# uacs.net
KiCad netlist of a schematic drawn in EAGLE
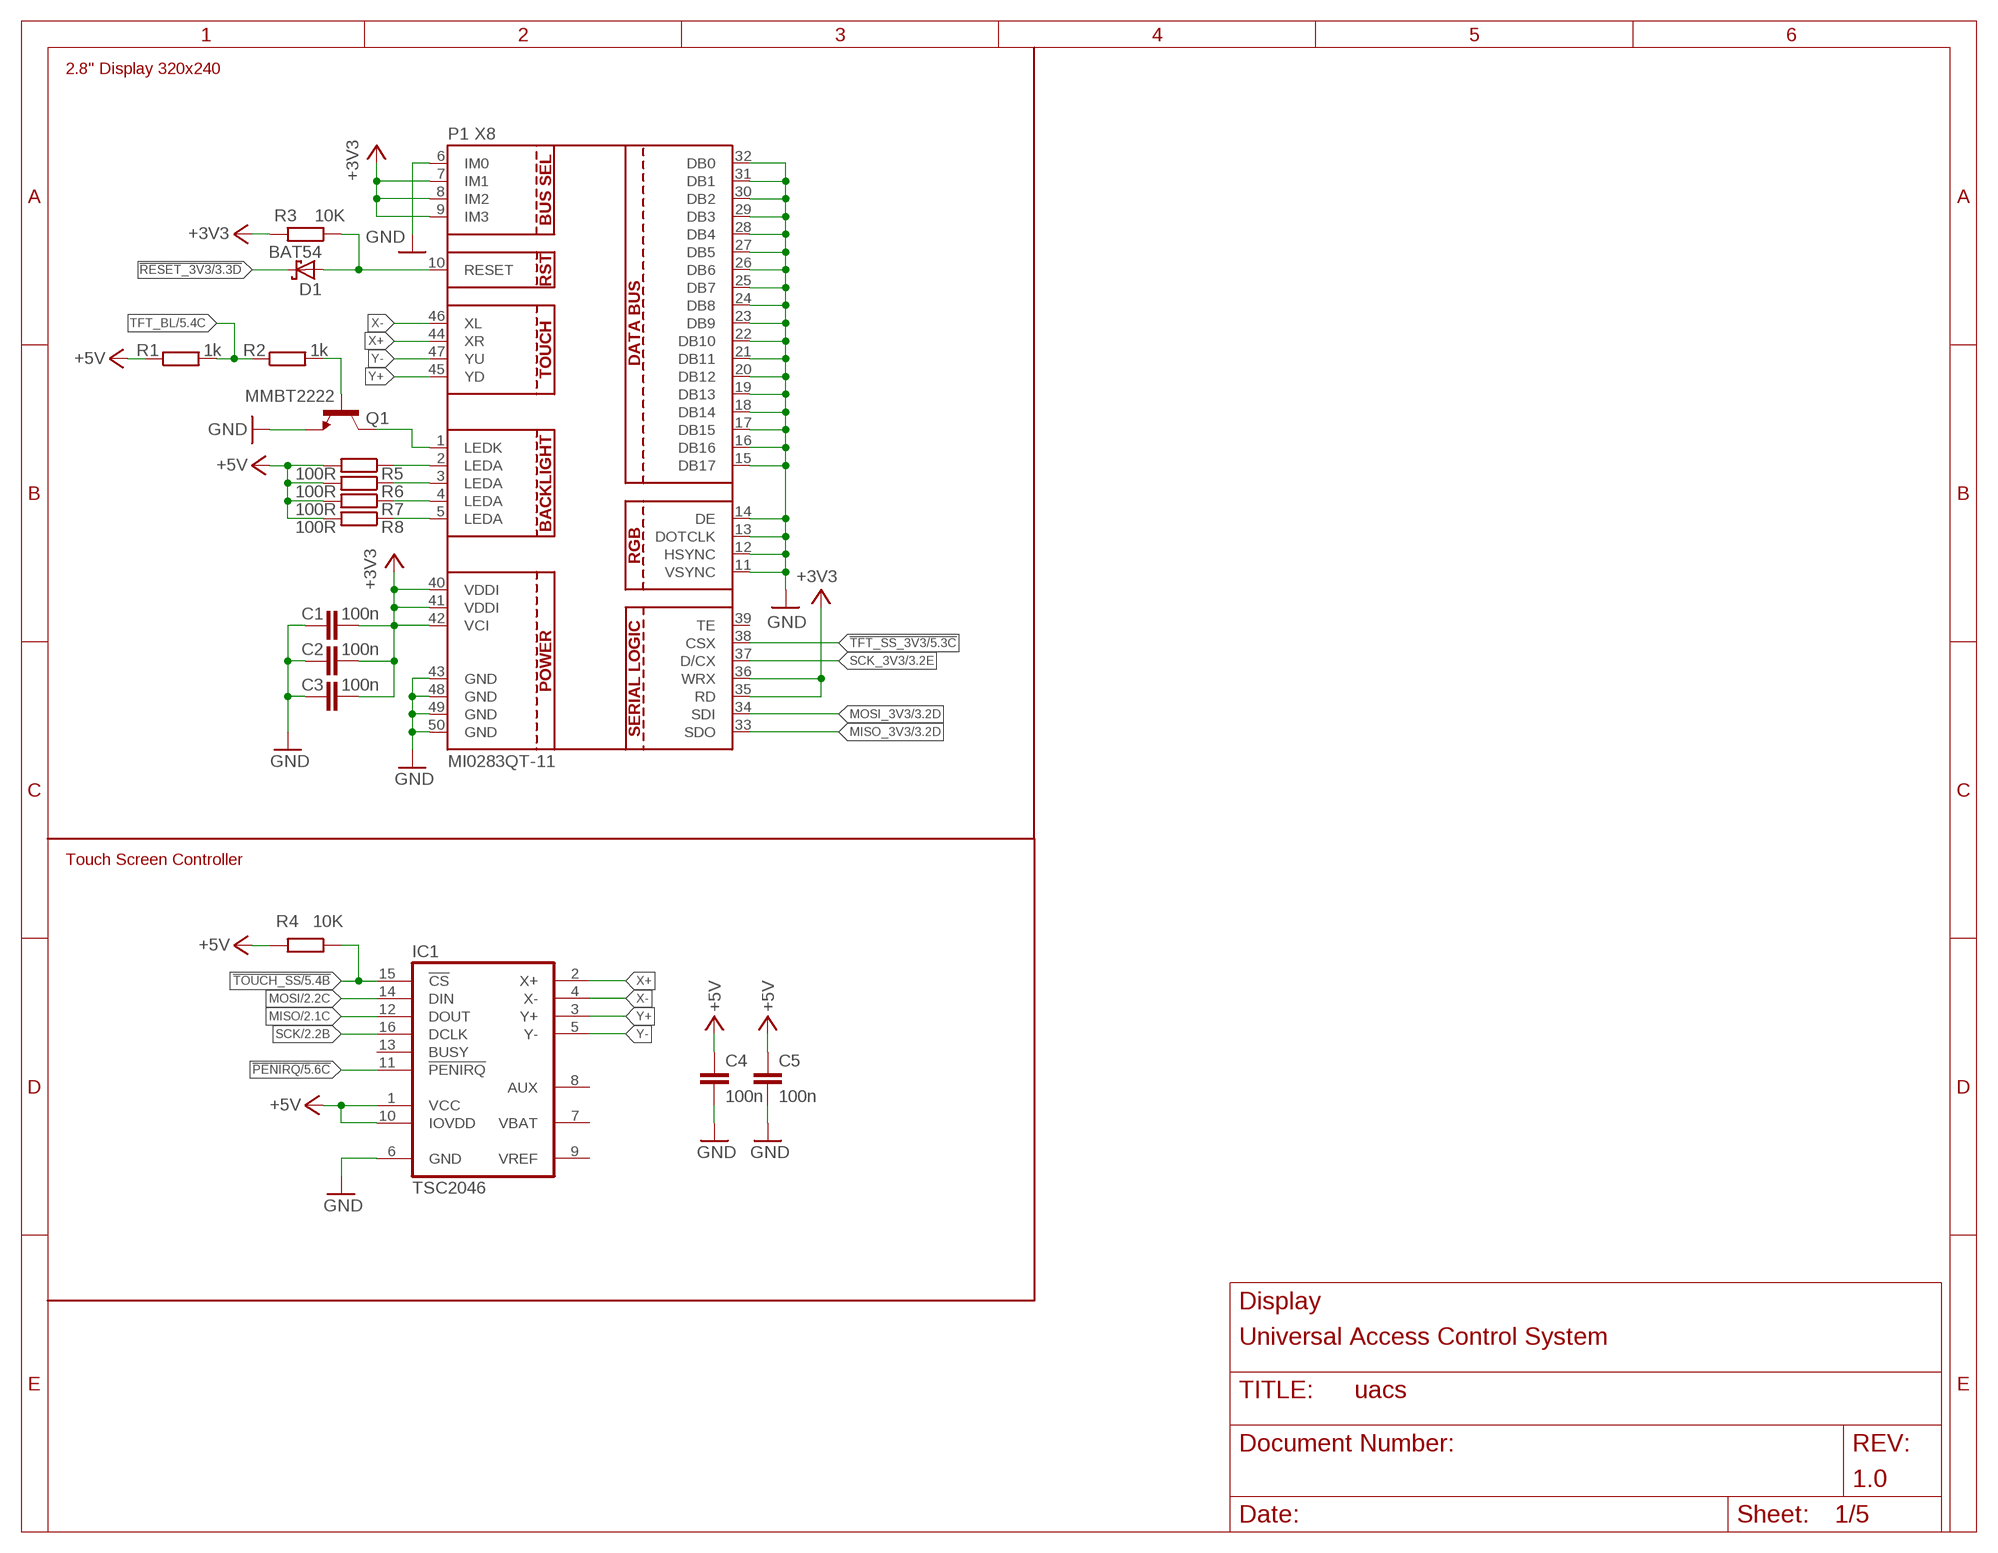
[diagram p0: schematic, sheet 1]
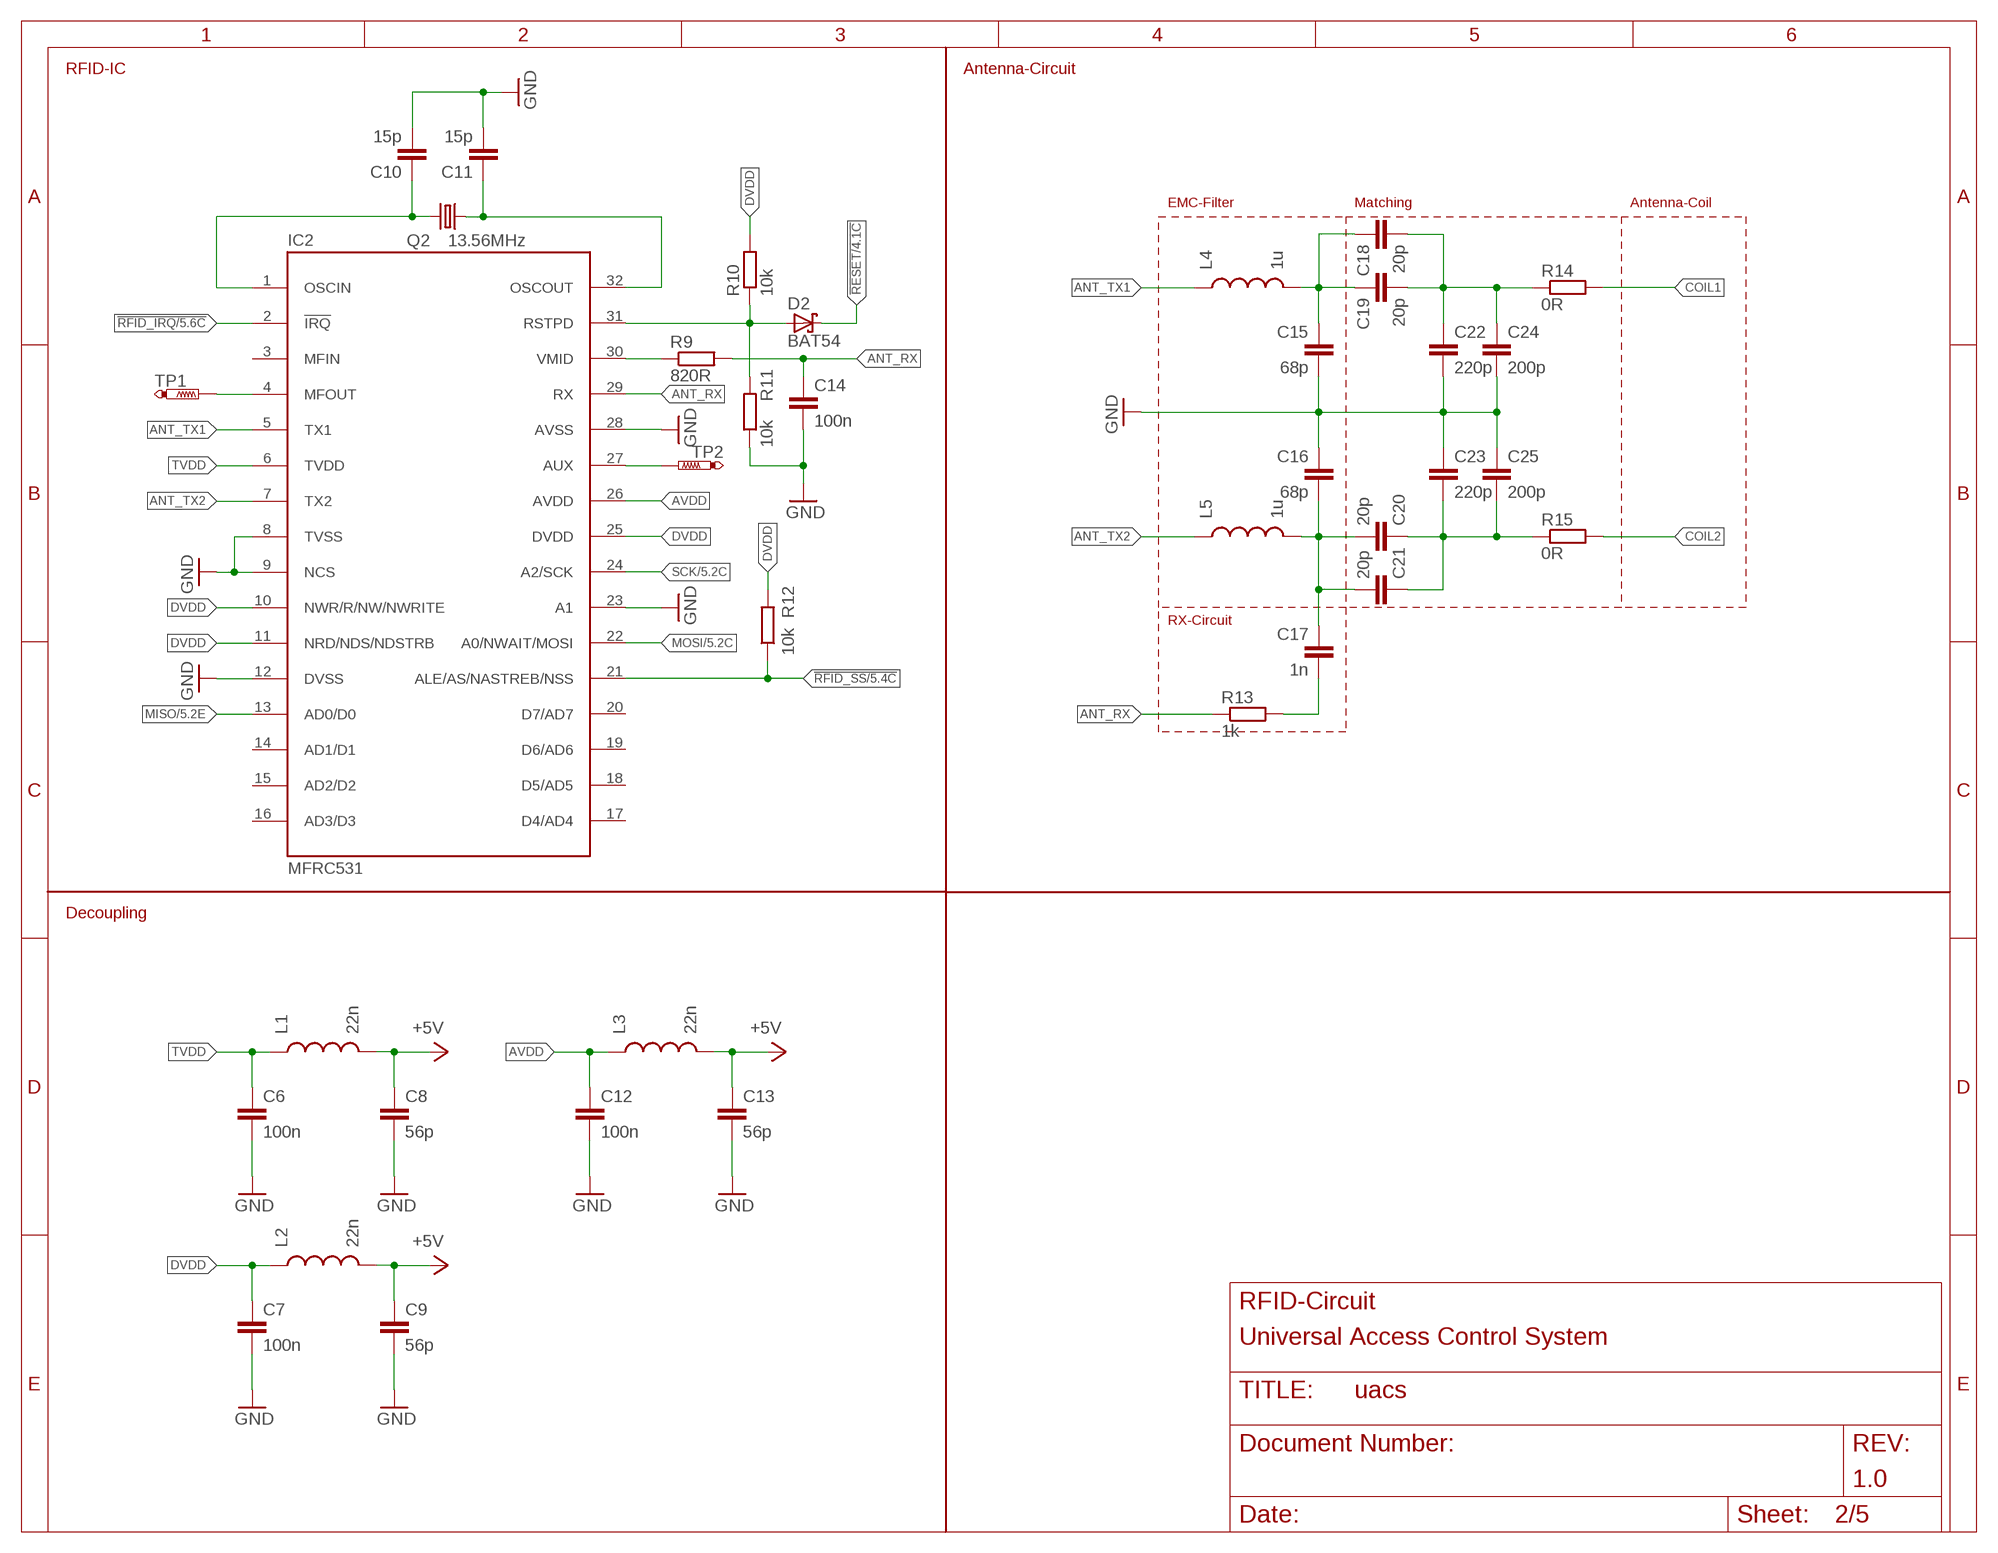
[diagram p1: schematic, sheet 2]
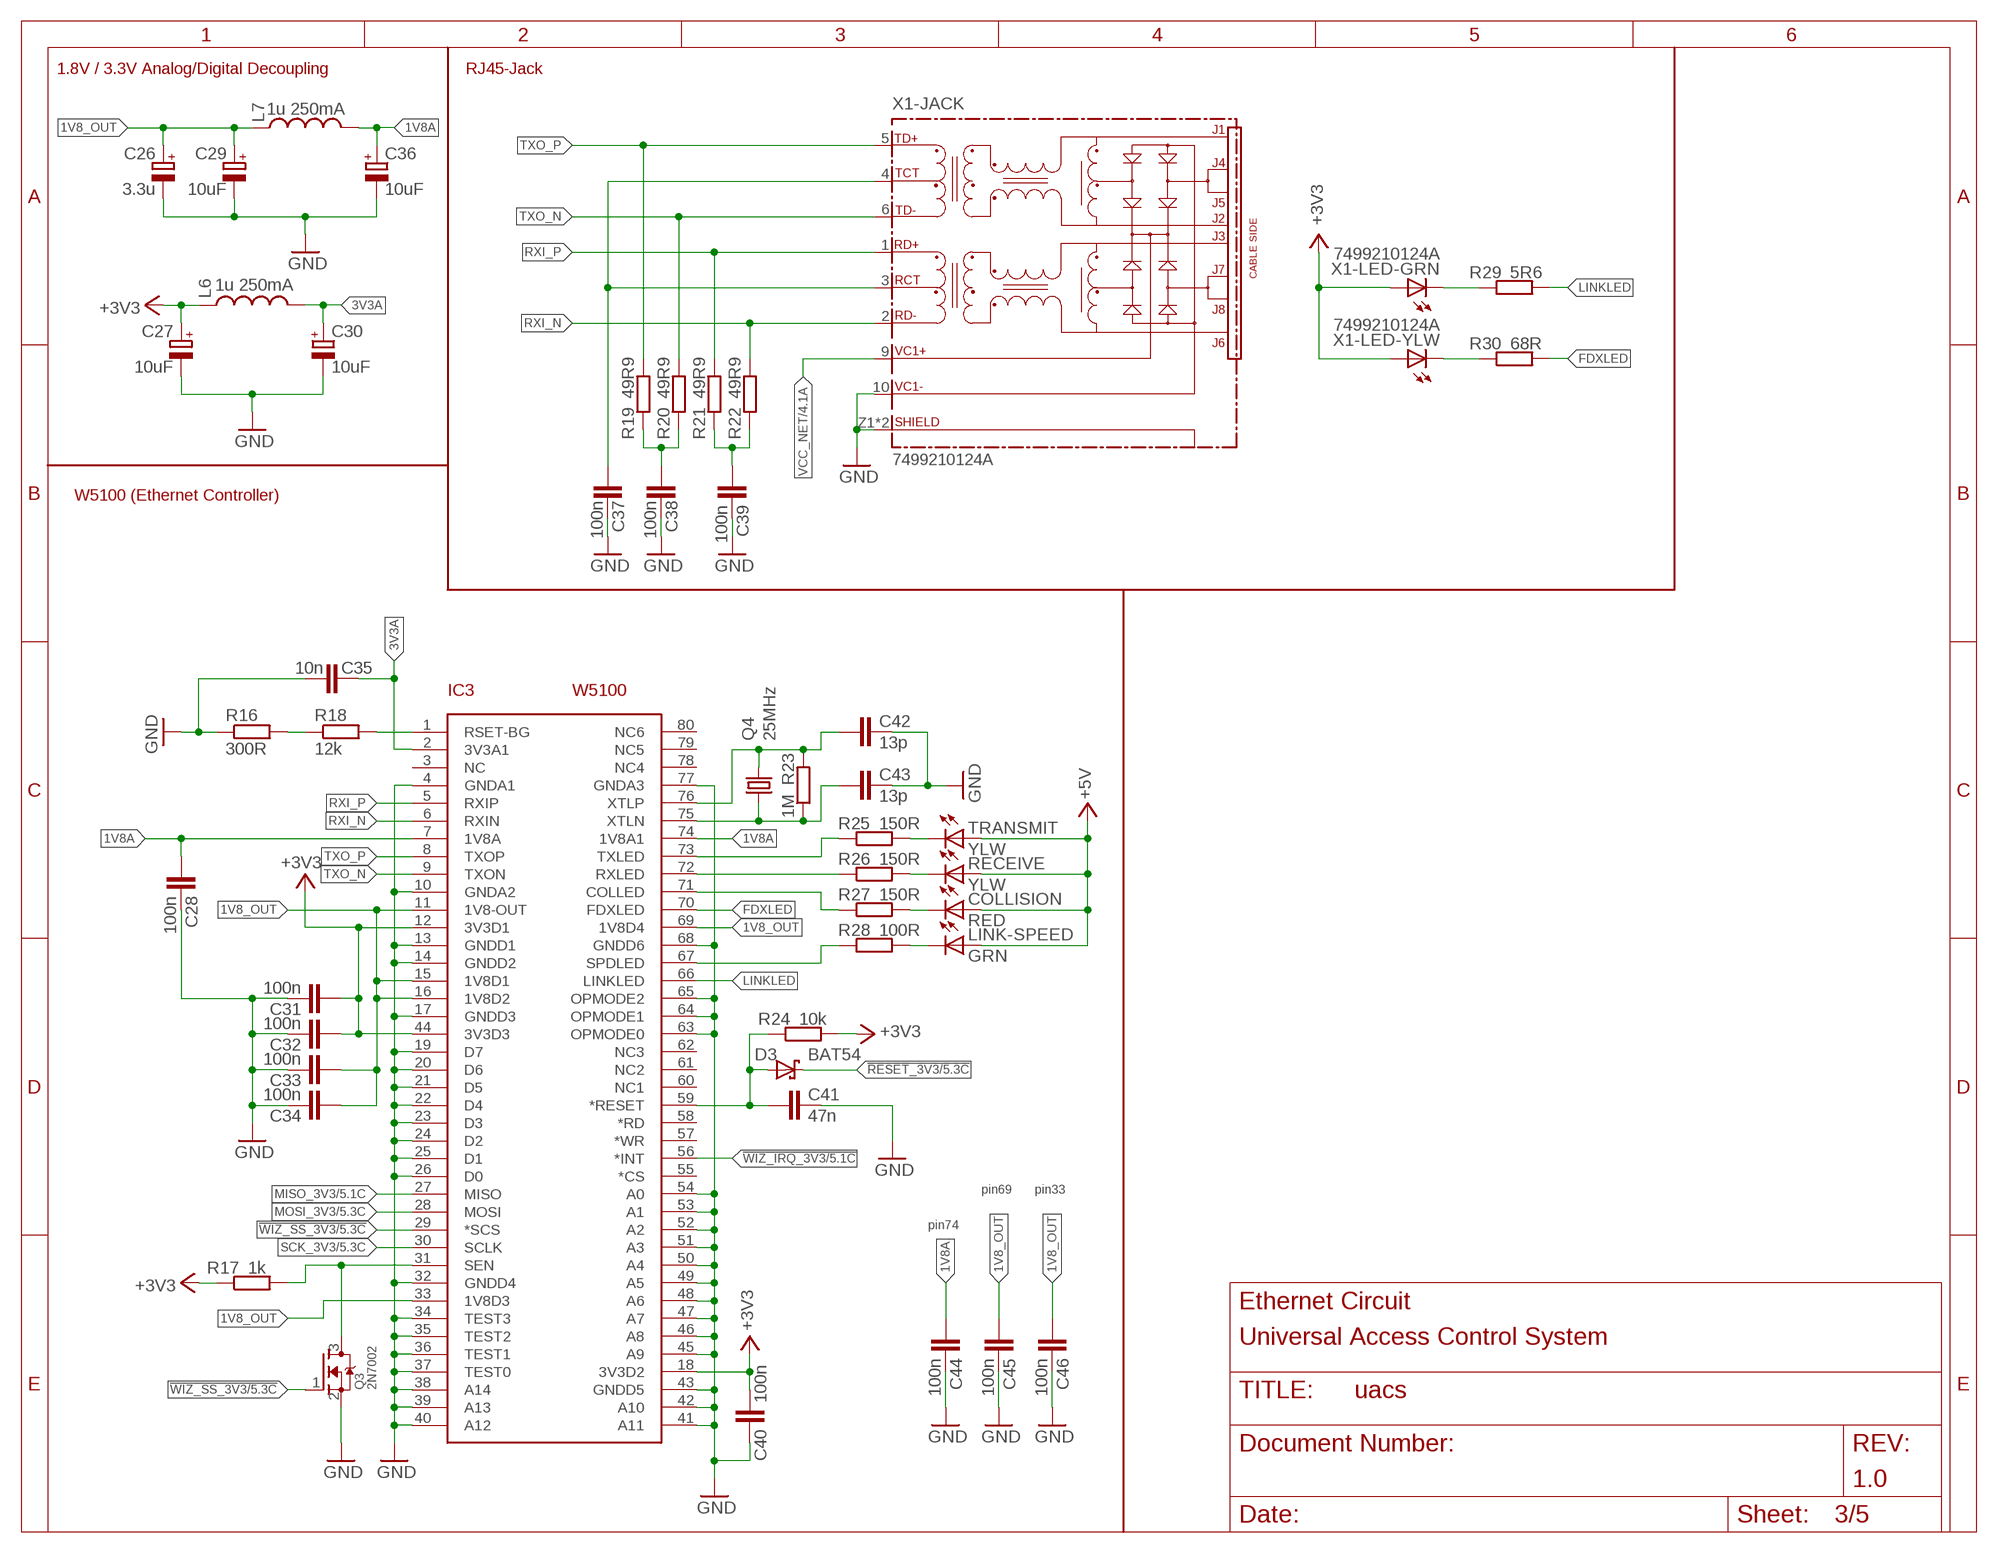
[diagram p2: schematic, sheet 3]
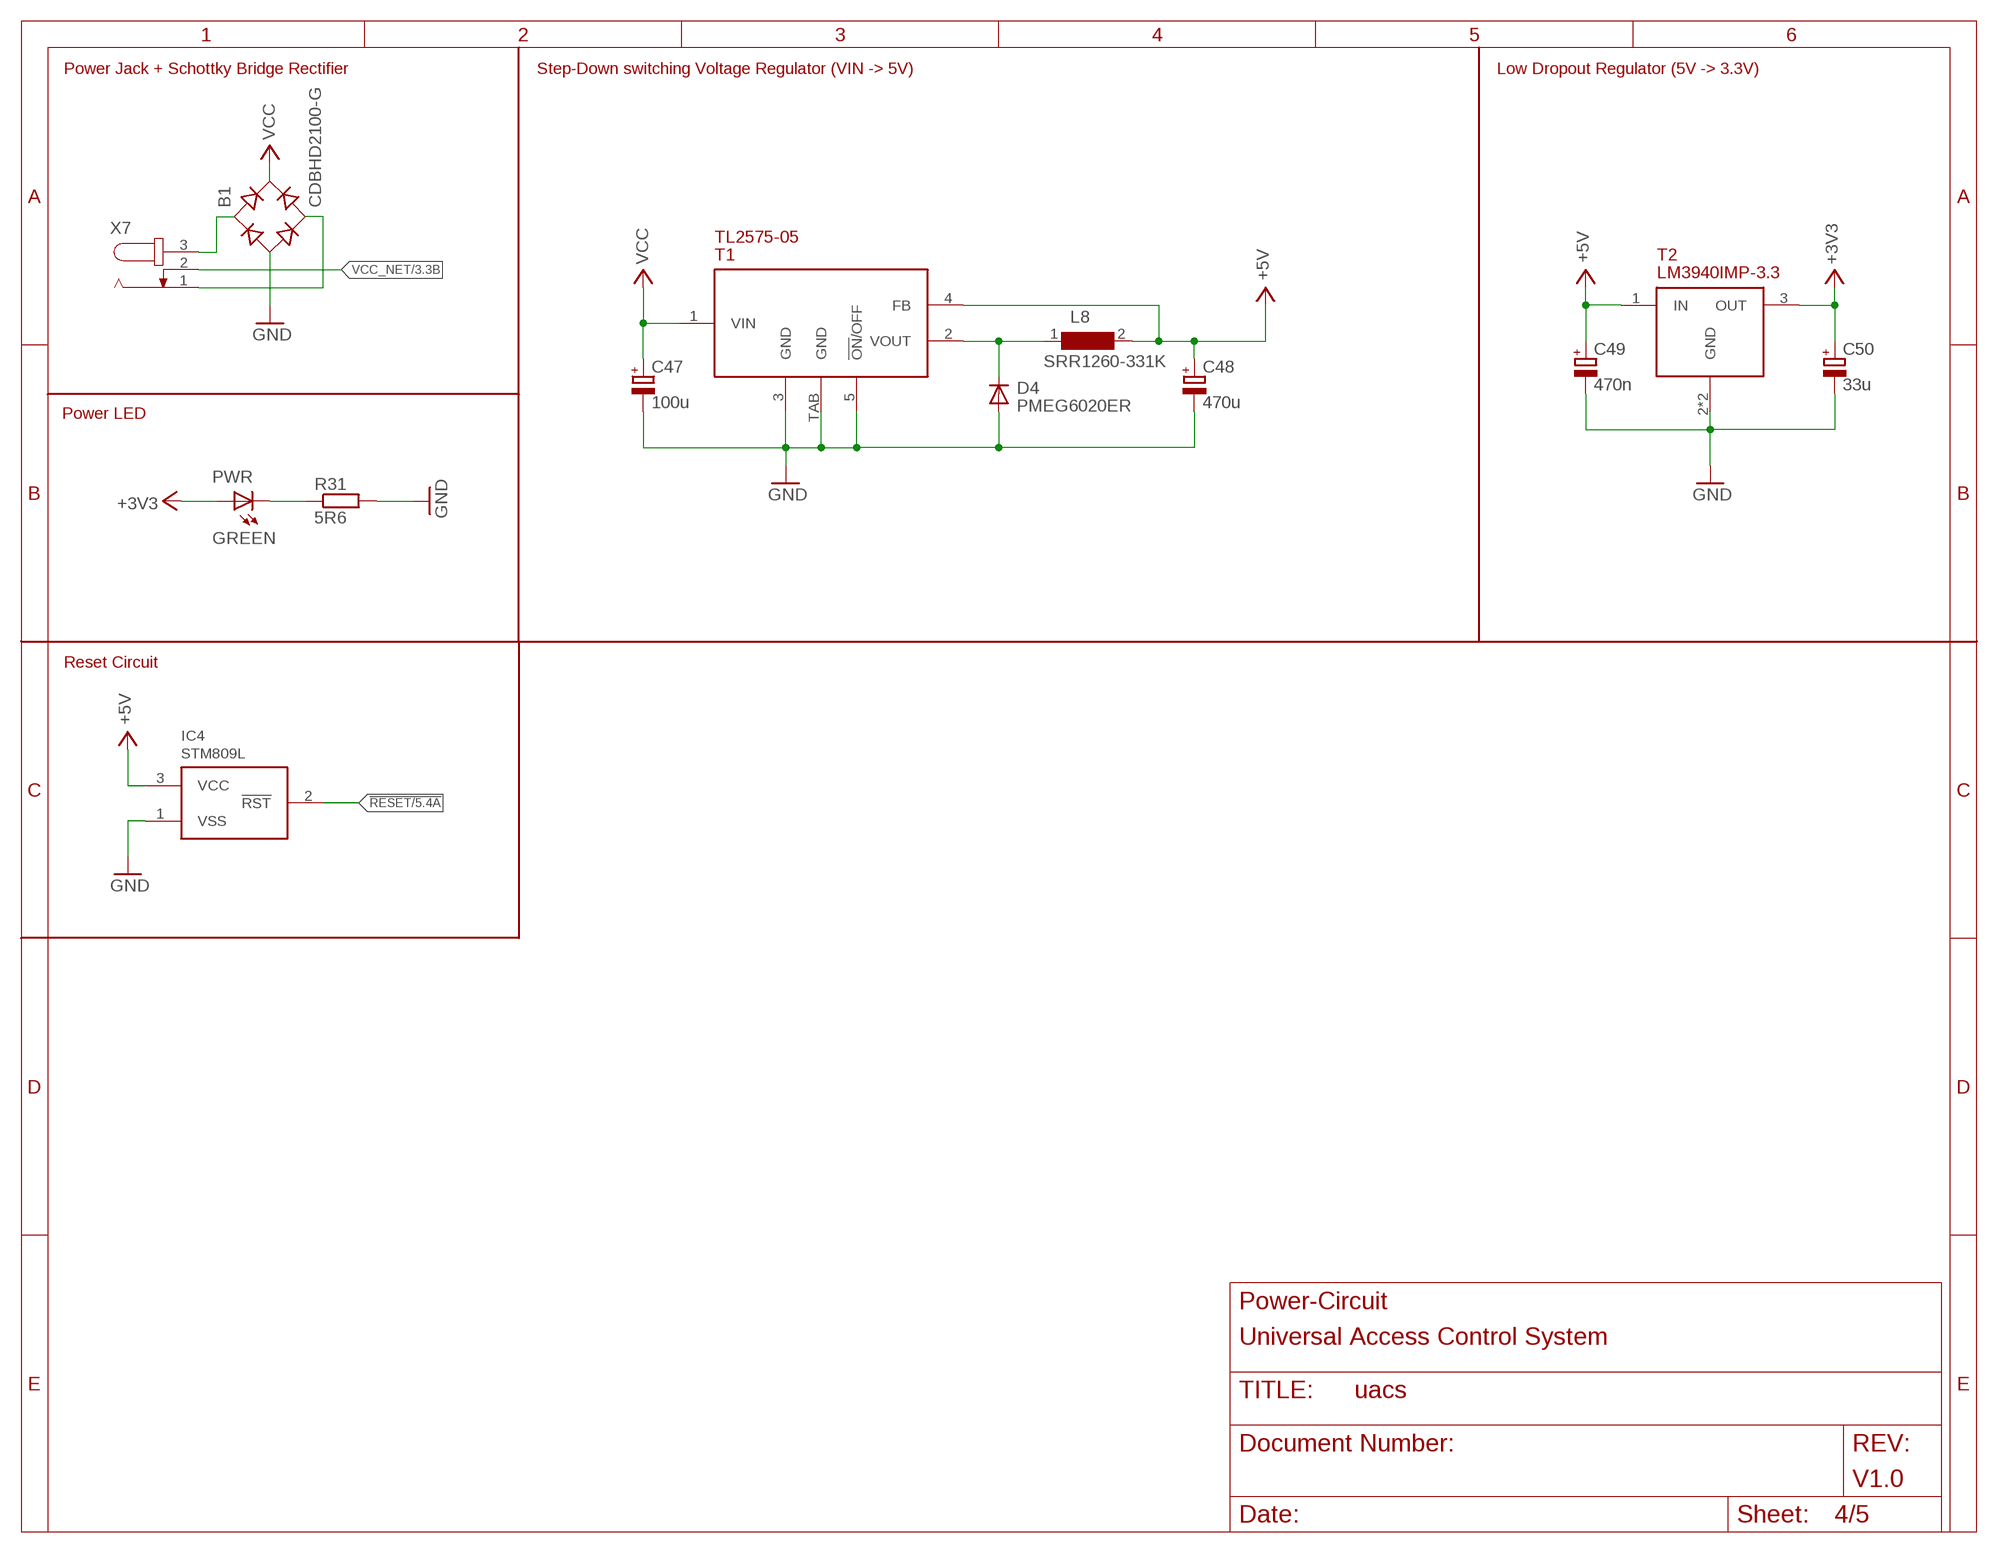
[diagram p3: schematic, sheet 4]
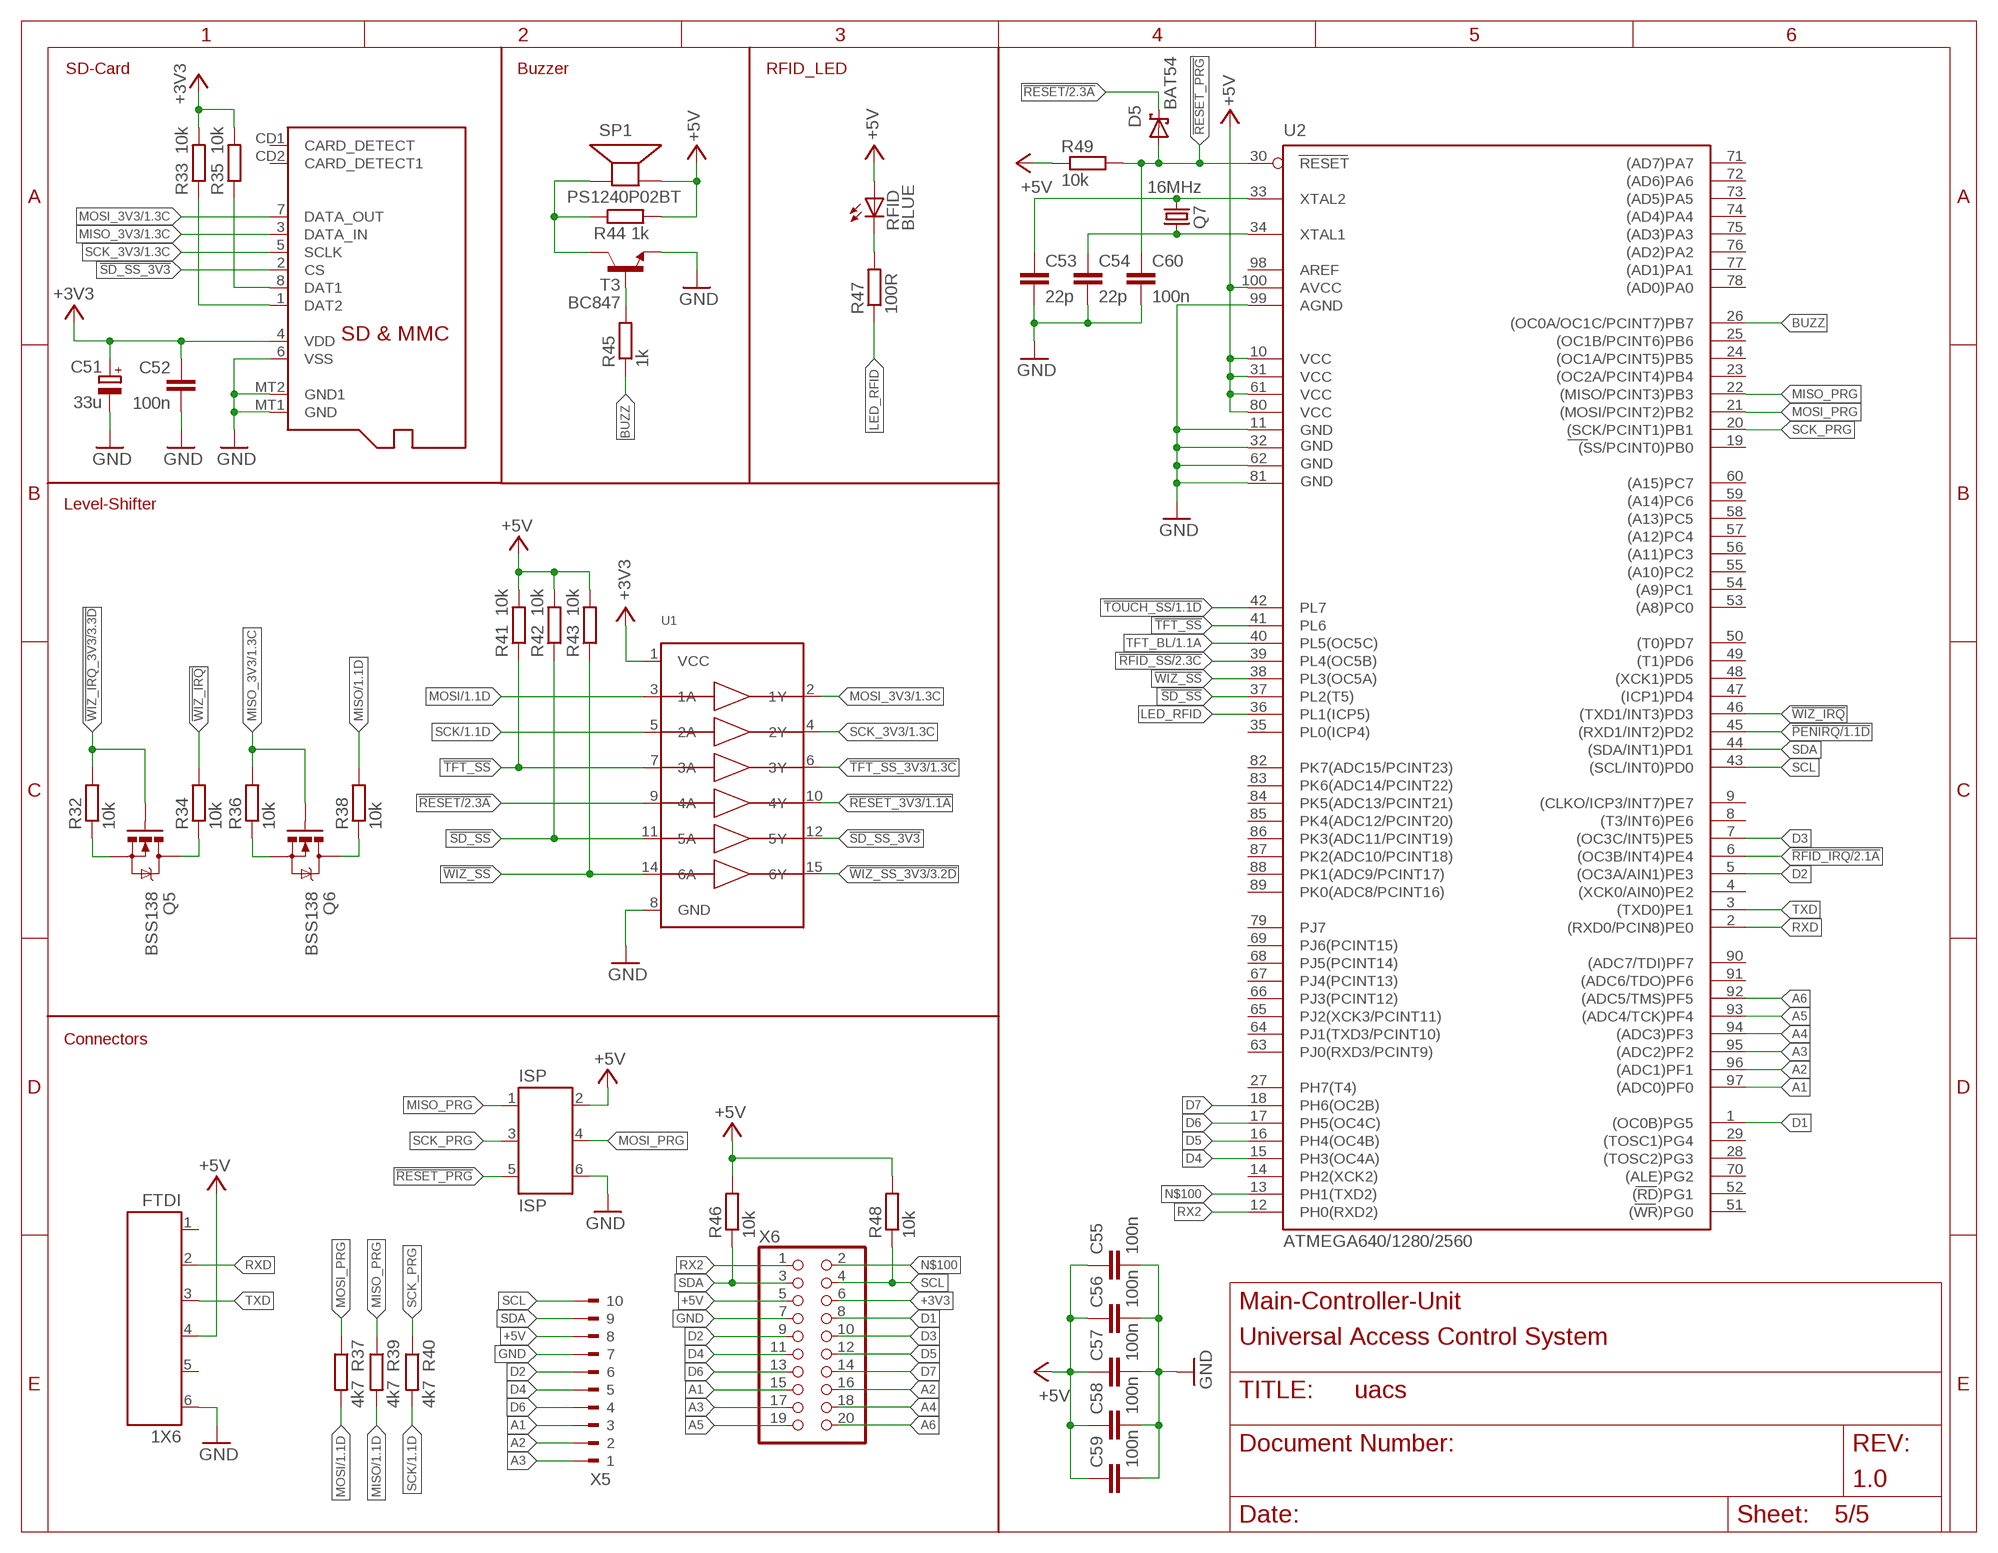
[diagram p4: schematic, sheet 5]

(export (version "E")
  (design (tool "Eeschema 10.0.6"))
  (components
    (comp (ref "C51")
      (value "33u")
      (footprint "eagle-import:C_6032-28R")
      (libsource (lib "eagle-import") (part "CPOL-EUC/6032-28R"))
    )
    (comp (ref "C52")
      (value "100n")
      (footprint "eagle-import:C0603")
      (libsource (lib "eagle-import") (part "C-EUC0603"))
    )
    (comp (ref "C53")
      (value "22p")
      (footprint "eagle-import:C0603")
      (libsource (lib "eagle-import") (part "C-EUC0603"))
    )
    (comp (ref "C54")
      (value "22p")
      (footprint "eagle-import:C0603")
      (libsource (lib "eagle-import") (part "C-EUC0603"))
    )
    (comp (ref "C55")
      (value "100n")
      (footprint "eagle-import:C0603")
      (libsource (lib "eagle-import") (part "C-EUC0603"))
    )
    (comp (ref "C56")
      (value "100n")
      (footprint "eagle-import:C0603")
      (libsource (lib "eagle-import") (part "C-EUC0603"))
    )
    (comp (ref "C57")
      (value "100n")
      (footprint "eagle-import:C0603")
      (libsource (lib "eagle-import") (part "C-EUC0603"))
    )
    (comp (ref "C58")
      (value "100n")
      (footprint "eagle-import:C0603")
      (libsource (lib "eagle-import") (part "C-EUC0603"))
    )
    (comp (ref "C59")
      (value "100n")
      (footprint "eagle-import:C0603")
      (libsource (lib "eagle-import") (part "C-EUC0603"))
    )
    (comp (ref "C60")
      (value "100n")
      (footprint "eagle-import:C0603")
      (libsource (lib "eagle-import") (part "C-EUC0603"))
    )
    (comp (ref "D5")
      (value "BAT54")
      (footprint "eagle-import:SOT23")
      (libsource (lib "eagle-import") (part "BAT54"))
    )
    (comp (ref "FTDI")
      (value "1X6")
      (footprint "eagle-import:1X6")
      (libsource (lib "eagle-import") (part "1X6"))
    )
    (comp (ref "ISP")
      (value "ISP")
      (footprint "eagle-import:2X3")
      (libsource (lib "eagle-import") (part "2X3"))
    )
    (comp (ref "Q5")
      (value "BSS138")
      (footprint "eagle-import:SOT23")
      (libsource (lib "eagle-import") (part "MOSFET-NCHANNELBSS138"))
    )
    (comp (ref "Q6")
      (value "BSS138")
      (footprint "eagle-import:SOT23")
      (libsource (lib "eagle-import") (part "MOSFET-NCHANNELBSS138"))
    )
    (comp (ref "Q7")
      (value "16MHz")
      (footprint "eagle-import:SM49")
      (libsource (lib "eagle-import") (part "CRYSTALSM49"))
    )
    (comp (ref "R32")
      (value "10k")
      (footprint "eagle-import:R0603")
      (libsource (lib "eagle-import") (part "R-EU_R0603"))
    )
    (comp (ref "R33")
      (value "10k")
      (footprint "eagle-import:R0603")
      (libsource (lib "eagle-import") (part "R-EU_R0603"))
    )
    (comp (ref "R34")
      (value "10k")
      (footprint "eagle-import:R0603")
      (libsource (lib "eagle-import") (part "R-EU_R0603"))
    )
    (comp (ref "R35")
      (value "10k")
      (footprint "eagle-import:R0603")
      (libsource (lib "eagle-import") (part "R-EU_R0603"))
    )
    (comp (ref "R36")
      (value "10k")
      (footprint "eagle-import:R0603")
      (libsource (lib "eagle-import") (part "R-EU_R0603"))
    )
    (comp (ref "R37")
      (value "4k7")
      (footprint "eagle-import:R0603")
      (libsource (lib "eagle-import") (part "R-EU_R0603"))
    )
    (comp (ref "R38")
      (value "10k")
      (footprint "eagle-import:R0603")
      (libsource (lib "eagle-import") (part "R-EU_R0603"))
    )
    (comp (ref "R39")
      (value "4k7")
      (footprint "eagle-import:R0603")
      (libsource (lib "eagle-import") (part "R-EU_R0603"))
    )
    (comp (ref "R40")
      (value "4k7")
      (footprint "eagle-import:R0603")
      (libsource (lib "eagle-import") (part "R-EU_R0603"))
    )
    (comp (ref "R41")
      (value "10k")
      (footprint "eagle-import:R0603")
      (libsource (lib "eagle-import") (part "R-EU_R0603"))
    )
    (comp (ref "R42")
      (value "10k")
      (footprint "eagle-import:R0603")
      (libsource (lib "eagle-import") (part "R-EU_R0603"))
    )
    (comp (ref "R43")
      (value "10k")
      (footprint "eagle-import:R0603")
      (libsource (lib "eagle-import") (part "R-EU_R0603"))
    )
    (comp (ref "R44")
      (value "1k")
      (footprint "eagle-import:R0603")
      (libsource (lib "eagle-import") (part "R-EU_R0603"))
    )
    (comp (ref "R45")
      (value "1k")
      (footprint "eagle-import:R0603")
      (libsource (lib "eagle-import") (part "R-EU_R0603"))
    )
    (comp (ref "R46")
      (value "10k")
      (footprint "eagle-import:R0603")
      (libsource (lib "eagle-import") (part "R-EU_R0603"))
    )
    (comp (ref "R47")
      (value "100R")
      (footprint "eagle-import:R0603")
      (libsource (lib "eagle-import") (part "R-EU_R0603"))
    )
    (comp (ref "R48")
      (value "10k")
      (footprint "eagle-import:R0603")
      (libsource (lib "eagle-import") (part "R-EU_R0603"))
    )
    (comp (ref "R49")
      (value "10k")
      (footprint "eagle-import:R0603")
      (libsource (lib "eagle-import") (part "R-EU_R0603"))
    )
    (comp (ref "RFID")
      (value "BLUE")
      (footprint "eagle-import:CHIPLED_0603")
      (libsource (lib "eagle-import") (part "LEDCHIPLED_0603"))
    )
    (comp (ref "SP1")
      (value "PS1240P02BT")
      (footprint "eagle-import:PS12")
      (libsource (lib "eagle-import") (part "SPEAKER/PS12"))
    )
    (comp (ref "T3")
      (value "BC847")
      (footprint "eagle-import:SOT23")
      (libsource (lib "eagle-import") (part "BC847"))
    )
    (comp (ref "U1")
      (value "74HC4050DTSSOP")
      (footprint "eagle-import:TSSOP16")
      (libsource (lib "eagle-import") (part "74HC4050DTSSOP"))
    )
    (comp (ref "U2")
      (value "ATMEGA640/1280/2560")
      (footprint "eagle-import:TQFP100")
      (libsource (lib "eagle-import") (part "ATMEGA2560AU"))
    )
    (comp (ref "X3")
      (value "MICROSD")
      (footprint "eagle-import:MICROSD")
      (libsource (lib "eagle-import") (part "MICROSD"))
    )
    (comp (ref "X5")
      (value "180-10")
      (footprint "eagle-import:180-10")
      (libsource (lib "eagle-import") (part "180-10"))
    )
    (comp (ref "X6")
      (value "PINHD-2X10")
      (footprint "eagle-import:2X10")
      (libsource (lib "eagle-import") (part "PINHD-2X10"))
    )
    (comp (ref "C6")
      (value "100n")
      (footprint "eagle-import:C0603")
      (libsource (lib "eagle-import") (part "C-EUC0603"))
    )
    (comp (ref "C7")
      (value "100n")
      (footprint "eagle-import:C0603")
      (libsource (lib "eagle-import") (part "C-EUC0603"))
    )
    (comp (ref "C8")
      (value "56p")
      (footprint "eagle-import:C0603")
      (libsource (lib "eagle-import") (part "C-EUC0603"))
    )
    (comp (ref "C9")
      (value "56p")
      (footprint "eagle-import:C0603")
      (libsource (lib "eagle-import") (part "C-EUC0603"))
    )
    (comp (ref "C10")
      (value "15p")
      (footprint "eagle-import:C0603")
      (libsource (lib "eagle-import") (part "C-EUC0603"))
    )
    (comp (ref "C11")
      (value "15p")
      (footprint "eagle-import:C0603")
      (libsource (lib "eagle-import") (part "C-EUC0603"))
    )
    (comp (ref "C12")
      (value "100n")
      (footprint "eagle-import:C0603")
      (libsource (lib "eagle-import") (part "C-EUC0603"))
    )
    (comp (ref "C13")
      (value "56p")
      (footprint "eagle-import:C0603")
      (libsource (lib "eagle-import") (part "C-EUC0603"))
    )
    (comp (ref "C14")
      (value "100n")
      (footprint "eagle-import:C0603")
      (libsource (lib "eagle-import") (part "C-EUC0603"))
    )
    (comp (ref "C15")
      (value "68p")
      (footprint "eagle-import:C0603")
      (libsource (lib "eagle-import") (part "C-EUC0603"))
    )
    (comp (ref "C16")
      (value "68p")
      (footprint "eagle-import:C0603")
      (libsource (lib "eagle-import") (part "C-EUC0603"))
    )
    (comp (ref "C17")
      (value "1n")
      (footprint "eagle-import:C0603")
      (libsource (lib "eagle-import") (part "C-EUC0603"))
    )
    (comp (ref "C18")
      (value "20p")
      (footprint "eagle-import:C0603")
      (libsource (lib "eagle-import") (part "C-EUC0603"))
    )
    (comp (ref "C19")
      (value "20p")
      (footprint "eagle-import:C0603")
      (libsource (lib "eagle-import") (part "C-EUC0603"))
    )
    (comp (ref "C20")
      (value "20p")
      (footprint "eagle-import:C0603")
      (libsource (lib "eagle-import") (part "C-EUC0603"))
    )
    (comp (ref "C21")
      (value "20p")
      (footprint "eagle-import:C0603")
      (libsource (lib "eagle-import") (part "C-EUC0603"))
    )
    (comp (ref "C22")
      (value "220p")
      (footprint "eagle-import:C0603")
      (libsource (lib "eagle-import") (part "C-EUC0603"))
    )
    (comp (ref "C23")
      (value "220p")
      (footprint "eagle-import:C0603")
      (libsource (lib "eagle-import") (part "C-EUC0603"))
    )
    (comp (ref "C24")
      (value "200p")
      (footprint "eagle-import:C0603")
      (libsource (lib "eagle-import") (part "C-EUC0603"))
    )
    (comp (ref "C25")
      (value "200p")
      (footprint "eagle-import:C0603")
      (libsource (lib "eagle-import") (part "C-EUC0603"))
    )
    (comp (ref "D2")
      (value "BAT54")
      (footprint "eagle-import:SOT23")
      (libsource (lib "eagle-import") (part "BAT54"))
    )
    (comp (ref "IC2")
      (value "MFRC531")
      (footprint "eagle-import:SO32")
      (libsource (lib "eagle-import") (part "MFRC531"))
    )
    (comp (ref "L1")
      (value "22n")
      (footprint "eagle-import:0603")
      (libsource (lib "eagle-import") (part "INDUCTOR0603"))
    )
    (comp (ref "L2")
      (value "22n")
      (footprint "eagle-import:0603")
      (libsource (lib "eagle-import") (part "INDUCTOR0603"))
    )
    (comp (ref "L3")
      (value "22n")
      (footprint "eagle-import:0603")
      (libsource (lib "eagle-import") (part "INDUCTOR0603"))
    )
    (comp (ref "L4")
      (value "1u")
      (footprint "eagle-import:0603")
      (libsource (lib "eagle-import") (part "INDUCTOR0603"))
    )
    (comp (ref "L5")
      (value "1u")
      (footprint "eagle-import:0603")
      (libsource (lib "eagle-import") (part "INDUCTOR0603"))
    )
    (comp (ref "Q2")
      (value "13.56MHz")
      (footprint "eagle-import:SM49")
      (libsource (lib "eagle-import") (part "CRYSTALSM49"))
    )
    (comp (ref "R9")
      (value "820R")
      (footprint "eagle-import:R0603")
      (libsource (lib "eagle-import") (part "R-EU_R0603"))
    )
    (comp (ref "R10")
      (value "10k")
      (footprint "eagle-import:R0603")
      (libsource (lib "eagle-import") (part "R-EU_R0603"))
    )
    (comp (ref "R11")
      (value "10k")
      (footprint "eagle-import:R0603")
      (libsource (lib "eagle-import") (part "R-EU_R0603"))
    )
    (comp (ref "R12")
      (value "10k")
      (footprint "eagle-import:R0603")
      (libsource (lib "eagle-import") (part "R-EU_R0603"))
    )
    (comp (ref "R13")
      (value "1k")
      (footprint "eagle-import:R0603")
      (libsource (lib "eagle-import") (part "R-EU_R0603"))
    )
    (comp (ref "R14")
      (value "0R")
      (footprint "eagle-import:R0603")
      (libsource (lib "eagle-import") (part "R-EU_R0603"))
    )
    (comp (ref "R15")
      (value "0R")
      (footprint "eagle-import:R0603")
      (libsource (lib "eagle-import") (part "R-EU_R0603"))
    )
    (comp (ref "TP1")
      (value "PTR1B1,27")
      (footprint "eagle-import:B1,27")
      (libsource (lib "eagle-import") (part "PTR1B1,27"))
    )
    (comp (ref "TP2")
      (value "PTR1B1,27")
      (footprint "eagle-import:B1,27")
      (libsource (lib "eagle-import") (part "PTR1B1,27"))
    )
    (comp (ref "C26")
      (value "3.3u")
      (footprint "eagle-import:B_3528-21R")
      (libsource (lib "eagle-import") (part "CPOL-EUB/3528-21R"))
    )
    (comp (ref "C27")
      (value "10uF")
      (footprint "eagle-import:B_3528-21R")
      (libsource (lib "eagle-import") (part "CPOL-EUB/3528-21R"))
    )
    (comp (ref "C28")
      (value "100n")
      (footprint "eagle-import:C0603")
      (libsource (lib "eagle-import") (part "C-EUC0603"))
    )
    (comp (ref "C29")
      (value "10uF")
      (footprint "eagle-import:B_3528-21R")
      (libsource (lib "eagle-import") (part "CPOL-EUB/3528-21R"))
    )
    (comp (ref "C30")
      (value "10uF")
      (footprint "eagle-import:B_3528-21R")
      (libsource (lib "eagle-import") (part "CPOL-EUB/3528-21R"))
    )
    (comp (ref "C31")
      (value "100n")
      (footprint "eagle-import:C0603")
      (libsource (lib "eagle-import") (part "C-EUC0603"))
    )
    (comp (ref "C32")
      (value "100n")
      (footprint "eagle-import:C0603")
      (libsource (lib "eagle-import") (part "C-EUC0603"))
    )
    (comp (ref "C33")
      (value "100n")
      (footprint "eagle-import:C0603")
      (libsource (lib "eagle-import") (part "C-EUC0603"))
    )
    (comp (ref "C34")
      (value "100n")
      (footprint "eagle-import:C0603")
      (libsource (lib "eagle-import") (part "C-EUC0603"))
    )
    (comp (ref "C35")
      (value "10n")
      (footprint "eagle-import:C0603")
      (libsource (lib "eagle-import") (part "C-EUC0603"))
    )
    (comp (ref "C36")
      (value "10uF")
      (footprint "eagle-import:B_3528-21R")
      (libsource (lib "eagle-import") (part "CPOL-EUB/3528-21R"))
    )
    (comp (ref "C37")
      (value "100n")
      (footprint "eagle-import:C0603")
      (libsource (lib "eagle-import") (part "C-EUC0603"))
    )
    (comp (ref "C38")
      (value "100n")
      (footprint "eagle-import:C0603")
      (libsource (lib "eagle-import") (part "C-EUC0603"))
    )
    (comp (ref "C39")
      (value "100n")
      (footprint "eagle-import:C0603")
      (libsource (lib "eagle-import") (part "C-EUC0603"))
    )
    (comp (ref "C40")
      (value "100n")
      (footprint "eagle-import:C0603")
      (libsource (lib "eagle-import") (part "C-EUC0603"))
    )
    (comp (ref "C41")
      (value "47n")
      (footprint "eagle-import:C0603")
      (libsource (lib "eagle-import") (part "C-EUC0603"))
    )
    (comp (ref "C42")
      (value "13p")
      (footprint "eagle-import:C0603")
      (libsource (lib "eagle-import") (part "C-EUC0603"))
    )
    (comp (ref "C43")
      (value "13p")
      (footprint "eagle-import:C0603")
      (libsource (lib "eagle-import") (part "C-EUC0603"))
    )
    (comp (ref "C44")
      (value "100n")
      (footprint "eagle-import:C0603")
      (libsource (lib "eagle-import") (part "C-EUC0603"))
    )
    (comp (ref "C45")
      (value "100n")
      (footprint "eagle-import:C0603")
      (libsource (lib "eagle-import") (part "C-EUC0603"))
    )
    (comp (ref "C46")
      (value "100n")
      (footprint "eagle-import:C0603")
      (libsource (lib "eagle-import") (part "C-EUC0603"))
    )
    (comp (ref "COLLISION")
      (value "RED")
      (footprint "eagle-import:CHIPLED_0603")
      (libsource (lib "eagle-import") (part "LEDCHIPLED_0603"))
    )
    (comp (ref "D3")
      (value "BAT54")
      (footprint "eagle-import:SOT23")
      (libsource (lib "eagle-import") (part "BAT54"))
    )
    (comp (ref "IC3")
      (value "W5100")
      (footprint "eagle-import:SQFP-S-10X10-80")
      (libsource (lib "eagle-import") (part "W5100"))
    )
    (comp (ref "L6")
      (value "1u 250mA")
      (footprint "eagle-import:0603")
      (libsource (lib "eagle-import") (part "INDUCTOR0603"))
    )
    (comp (ref "L7")
      (value "1u 250mA")
      (footprint "eagle-import:0603")
      (libsource (lib "eagle-import") (part "INDUCTOR0603"))
    )
    (comp (ref "LINK-SPEED")
      (value "GRN")
      (footprint "eagle-import:CHIPLED_0603")
      (libsource (lib "eagle-import") (part "LEDCHIPLED_0603"))
    )
    (comp (ref "Q3")
      (value "2N7002")
      (footprint "eagle-import:SOT23")
      (libsource (lib "eagle-import") (part "MOSFET-NREFLOW"))
    )
    (comp (ref "Q4")
      (value "25MHz")
      (footprint "eagle-import:SM49")
      (libsource (lib "eagle-import") (part "CRYSTALSM49"))
    )
    (comp (ref "R16")
      (value "300R")
      (footprint "eagle-import:R0603")
      (libsource (lib "eagle-import") (part "R-EU_R0603"))
    )
    (comp (ref "R17")
      (value "1k")
      (footprint "eagle-import:R0603")
      (libsource (lib "eagle-import") (part "R-EU_R0603"))
    )
    (comp (ref "R18")
      (value "12k")
      (footprint "eagle-import:R0603")
      (libsource (lib "eagle-import") (part "R-EU_R0603"))
    )
    (comp (ref "R19")
      (value "49R9")
      (footprint "eagle-import:R0603")
      (libsource (lib "eagle-import") (part "R-EU_R0603"))
    )
    (comp (ref "R20")
      (value "49R9")
      (footprint "eagle-import:R0603")
      (libsource (lib "eagle-import") (part "R-EU_R0603"))
    )
    (comp (ref "R21")
      (value "49R9")
      (footprint "eagle-import:R0603")
      (libsource (lib "eagle-import") (part "R-EU_R0603"))
    )
    (comp (ref "R22")
      (value "49R9")
      (footprint "eagle-import:R0603")
      (libsource (lib "eagle-import") (part "R-EU_R0603"))
    )
    (comp (ref "R23")
      (value "1M")
      (footprint "eagle-import:R0603")
      (libsource (lib "eagle-import") (part "R-EU_R0603"))
    )
    (comp (ref "R24")
      (value "10k")
      (footprint "eagle-import:R0603")
      (libsource (lib "eagle-import") (part "R-EU_R0603"))
    )
    (comp (ref "R25")
      (value "150R")
      (footprint "eagle-import:R0603")
      (libsource (lib "eagle-import") (part "R-EU_R0603"))
    )
    (comp (ref "R26")
      (value "150R")
      (footprint "eagle-import:R0603")
      (libsource (lib "eagle-import") (part "R-EU_R0603"))
    )
    (comp (ref "R27")
      (value "150R")
      (footprint "eagle-import:R0603")
      (libsource (lib "eagle-import") (part "R-EU_R0603"))
    )
    (comp (ref "R28")
      (value "100R")
      (footprint "eagle-import:R0603")
      (libsource (lib "eagle-import") (part "R-EU_R0603"))
    )
    (comp (ref "R29")
      (value "5R6")
      (footprint "eagle-import:R0603")
      (libsource (lib "eagle-import") (part "R-EU_R0603"))
    )
    (comp (ref "R30")
      (value "68R")
      (footprint "eagle-import:R0603")
      (libsource (lib "eagle-import") (part "R-EU_R0603"))
    )
    (comp (ref "RECEIVE")
      (value "YLW")
      (footprint "eagle-import:CHIPLED_0603")
      (libsource (lib "eagle-import") (part "LEDCHIPLED_0603"))
    )
    (comp (ref "TRANSMIT")
      (value "YLW")
      (footprint "eagle-import:CHIPLED_0603")
      (libsource (lib "eagle-import") (part "LEDCHIPLED_0603"))
    )
    (comp (ref "X1")
      (value "7499210124A")
      (footprint "eagle-import:7499210124A")
      (libsource (lib "eagle-import") (part "7499210124A"))
    )
    (comp (ref "C1")
      (value "100n")
      (footprint "eagle-import:C0603")
      (libsource (lib "eagle-import") (part "C-EUC0603"))
    )
    (comp (ref "C2")
      (value "100n")
      (footprint "eagle-import:C0603")
      (libsource (lib "eagle-import") (part "C-EUC0603"))
    )
    (comp (ref "C3")
      (value "100n")
      (footprint "eagle-import:C0603")
      (libsource (lib "eagle-import") (part "C-EUC0603"))
    )
    (comp (ref "C4")
      (value "100n")
      (footprint "eagle-import:C0603")
      (libsource (lib "eagle-import") (part "C-EUC0603"))
    )
    (comp (ref "C5")
      (value "100n")
      (footprint "eagle-import:C0603")
      (libsource (lib "eagle-import") (part "C-EUC0603"))
    )
    (comp (ref "D1")
      (value "BAT54")
      (footprint "eagle-import:SOT23")
      (libsource (lib "eagle-import") (part "BAT54"))
    )
    (comp (ref "IC1")
      (value "TSC2046")
      (footprint "eagle-import:TSSOP16")
      (libsource (lib "eagle-import") (part "TSC2046"))
    )
    (comp (ref "P1")
      (value "MI0283QT-11")
      (footprint "eagle-import:MI0283QT-11")
      (libsource (lib "eagle-import") (part "MI0283QT-11"))
    )
    (comp (ref "Q1")
      (value "MMBT2222")
      (footprint "eagle-import:SOT23-3")
      (libsource (lib "eagle-import") (part "TRANSISTOR_NPNMMBT2222A"))
    )
    (comp (ref "R1")
      (value "1k")
      (footprint "eagle-import:R0603")
      (libsource (lib "eagle-import") (part "R-EU_R0603"))
    )
    (comp (ref "R2")
      (value "1k")
      (footprint "eagle-import:R0603")
      (libsource (lib "eagle-import") (part "R-EU_R0603"))
    )
    (comp (ref "R3")
      (value "10K")
      (footprint "eagle-import:R0603")
      (libsource (lib "eagle-import") (part "R-EU_R0603"))
    )
    (comp (ref "R4")
      (value "10K")
      (footprint "eagle-import:R0603")
      (libsource (lib "eagle-import") (part "R-EU_R0603"))
    )
    (comp (ref "R5")
      (value "100R")
      (footprint "eagle-import:R0603")
      (libsource (lib "eagle-import") (part "R-EU_R0603"))
    )
    (comp (ref "R6")
      (value "100R")
      (footprint "eagle-import:R0603")
      (libsource (lib "eagle-import") (part "R-EU_R0603"))
    )
    (comp (ref "R7")
      (value "100R")
      (footprint "eagle-import:R0603")
      (libsource (lib "eagle-import") (part "R-EU_R0603"))
    )
    (comp (ref "R8")
      (value "100R")
      (footprint "eagle-import:R0603")
      (libsource (lib "eagle-import") (part "R-EU_R0603"))
    )
    (comp (ref "B1")
      (value "CDBHD2100-G")
      (footprint "eagle-import:MBS")
      (libsource (lib "eagle-import") (part "BS10"))
    )
    (comp (ref "C47")
      (value "100u")
      (footprint "eagle-import:PANASONIC_G")
      (libsource (lib "eagle-import") (part "CPOL-EUG"))
    )
    (comp (ref "C48")
      (value "470u")
      (footprint "eagle-import:PANASONIC_G")
      (libsource (lib "eagle-import") (part "CPOL-EUG"))
    )
    (comp (ref "C49")
      (value "470n")
      (footprint "eagle-import:PANASONIC_B")
      (libsource (lib "eagle-import") (part "CPOL-EUB"))
    )
    (comp (ref "C50")
      (value "33u")
      (footprint "eagle-import:PANASONIC_D")
      (libsource (lib "eagle-import") (part "CPOL-EUD"))
    )
    (comp (ref "D4")
      (value "PMEG6020ER")
      (footprint "eagle-import:SOD-123")
      (libsource (lib "eagle-import") (part "DIODESOD-123"))
    )
    (comp (ref "IC4")
      (value "STM809L")
      (footprint "eagle-import:SOT-23-3")
      (libsource (lib "eagle-import") (part "STM809"))
    )
    (comp (ref "L8")
      (value "SRR1260-331K")
      (footprint "eagle-import:WE-PD_1260_1245_1280_1210")
      (libsource (lib "eagle-import") (part "WE-PD_1260/1245/1280/1210"))
    )
    (comp (ref "PWR")
      (value "GREEN")
      (footprint "eagle-import:CHIPLED_0603")
      (libsource (lib "eagle-import") (part "LEDCHIPLED_0603"))
    )
    (comp (ref "R31")
      (value "5R6")
      (footprint "eagle-import:R0603")
      (libsource (lib "eagle-import") (part "R-EU_R0603"))
    )
    (comp (ref "T1")
      (value "TL2575-05")
      (footprint "eagle-import:TO-263-5")
      (libsource (lib "eagle-import") (part "TL2575-05"))
    )
    (comp (ref "T2")
      (value "LM3940IMP-3.3")
      (footprint "eagle-import:SOT223")
      (libsource (lib "eagle-import") (part "LM3940IMP-3.3"))
    )
    (comp (ref "X7")
      (value "JACK-PLUG1")
      (footprint "eagle-import:SPC4078")
      (libsource (lib "eagle-import") (part "JACK-PLUG1"))
    )
  )
  (nets
    (net (code "1") (name "+3V3") (class "Default")
      (node (ref "C1") (pin "2") (pinfunction "2_2") (pintype "passive"))
      (node (ref "C2") (pin "2") (pinfunction "2_2") (pintype "passive"))
      (node (ref "C27") (pin "+") (pinfunction "+_+") (pintype "passive"))
      (node (ref "C3") (pin "2") (pinfunction "2_2") (pintype "passive"))
      (node (ref "C31") (pin "1") (pinfunction "1_1") (pintype "passive"))
      (node (ref "C32") (pin "1") (pinfunction "1_1") (pintype "passive"))
      (node (ref "C40") (pin "1") (pinfunction "1_1") (pintype "passive"))
      (node (ref "C50") (pin "+") (pinfunction "+_+") (pintype "passive"))
      (node (ref "C51") (pin "+") (pinfunction "+_+") (pintype "passive"))
      (node (ref "C52") (pin "1") (pinfunction "1_1") (pintype "passive"))
      (node (ref "IC3") (pin "12") (pinfunction "3V3D1_12") (pintype "power_in"))
      (node (ref "IC3") (pin "18") (pinfunction "3V3D2_18") (pintype "power_in"))
      (node (ref "IC3") (pin "44") (pinfunction "3V3D3_44") (pintype "power_in"))
      (node (ref "L6") (pin "1") (pinfunction "1_1") (pintype "passive"))
      (node (ref "P1") (pin "35") (pinfunction "RD_35") (pintype "bidirectional"))
      (node (ref "P1") (pin "36") (pinfunction "WRX_36") (pintype "bidirectional"))
      (node (ref "P1") (pin "40") (pinfunction "VDDI_40") (pintype "bidirectional"))
      (node (ref "P1") (pin "41") (pinfunction "VDDI_41") (pintype "bidirectional"))
      (node (ref "P1") (pin "42") (pinfunction "VCI_42") (pintype "bidirectional"))
      (node (ref "P1") (pin "7") (pinfunction "IM1_7") (pintype "bidirectional"))
      (node (ref "P1") (pin "8") (pinfunction "IM2_8") (pintype "bidirectional"))
      (node (ref "P1") (pin "9") (pinfunction "IM3_9") (pintype "bidirectional"))
      (node (ref "PWR") (pin "A") (pinfunction "A_A") (pintype "passive"))
      (node (ref "R17") (pin "1") (pinfunction "1_1") (pintype "passive"))
      (node (ref "R24") (pin "2") (pinfunction "2_2") (pintype "passive"))
      (node (ref "R3") (pin "2") (pinfunction "2_2") (pintype "passive"))
      (node (ref "R33") (pin "2") (pinfunction "2_2") (pintype "passive"))
      (node (ref "R35") (pin "2") (pinfunction "2_2") (pintype "passive"))
      (node (ref "T2") (pin "3") (pinfunction "OUT_3") (pintype "power_in"))
      (node (ref "U1") (pin "1") (pinfunction "VCC_1") (pintype "bidirectional"))
      (node (ref "X1") (pin "12") (pinfunction "A_12") (pintype "passive"))
      (node (ref "X1") (pin "14") (pinfunction "A_14") (pintype "passive"))
      (node (ref "X3") (pin "4") (pinfunction "VDD_4") (pintype "power_in"))
      (node (ref "X6") (pin "6") (pinfunction "6_6") (pintype "passive"))
    )
    (net (code "2") (name "+5V") (class "Default")
      (node (ref "C13") (pin "1") (pinfunction "1_1") (pintype "passive"))
      (node (ref "C4") (pin "1") (pinfunction "1_1") (pintype "passive"))
      (node (ref "C48") (pin "+") (pinfunction "+_+") (pintype "passive"))
      (node (ref "C49") (pin "+") (pinfunction "+_+") (pintype "passive"))
      (node (ref "C5") (pin "1") (pinfunction "1_1") (pintype "passive"))
      (node (ref "C55") (pin "1") (pinfunction "1_1") (pintype "passive"))
      (node (ref "C56") (pin "1") (pinfunction "1_1") (pintype "passive"))
      (node (ref "C57") (pin "1") (pinfunction "1_1") (pintype "passive"))
      (node (ref "C58") (pin "1") (pinfunction "1_1") (pintype "passive"))
      (node (ref "C59") (pin "1") (pinfunction "1_1") (pintype "passive"))
      (node (ref "C8") (pin "1") (pinfunction "1_1") (pintype "passive"))
      (node (ref "C9") (pin "1") (pinfunction "1_1") (pintype "passive"))
      (node (ref "COLLISION") (pin "A") (pinfunction "A_A") (pintype "passive"))
      (node (ref "FTDI") (pin "4") (pinfunction "4_4") (pintype "bidirectional"))
      (node (ref "IC1") (pin "1") (pinfunction "VCC_1") (pintype "power_in"))
      (node (ref "IC1") (pin "10") (pinfunction "IOVDD_10") (pintype "power_in"))
      (node (ref "IC4") (pin "3") (pinfunction "VCC_3") (pintype "bidirectional"))
      (node (ref "ISP") (pin "2") (pinfunction "2_2") (pintype "bidirectional"))
      (node (ref "L1") (pin "2") (pinfunction "2_2") (pintype "passive"))
      (node (ref "L2") (pin "2") (pinfunction "2_2") (pintype "passive"))
      (node (ref "L3") (pin "2") (pinfunction "2_2") (pintype "passive"))
      (node (ref "L8") (pin "2") (pinfunction "2_2") (pintype "passive"))
      (node (ref "LINK-SPEED") (pin "A") (pinfunction "A_A") (pintype "passive"))
      (node (ref "R1") (pin "1") (pinfunction "1_1") (pintype "passive"))
      (node (ref "R4") (pin "2") (pinfunction "2_2") (pintype "passive"))
      (node (ref "R41") (pin "2") (pinfunction "2_2") (pintype "passive"))
      (node (ref "R42") (pin "2") (pinfunction "2_2") (pintype "passive"))
      (node (ref "R43") (pin "2") (pinfunction "2_2") (pintype "passive"))
      (node (ref "R44") (pin "2") (pinfunction "2_2") (pintype "passive"))
      (node (ref "R46") (pin "2") (pinfunction "2_2") (pintype "passive"))
      (node (ref "R48") (pin "2") (pinfunction "2_2") (pintype "passive"))
      (node (ref "R49") (pin "1") (pinfunction "1_1") (pintype "passive"))
      (node (ref "R5") (pin "2") (pinfunction "2_2") (pintype "passive"))
      (node (ref "R6") (pin "2") (pinfunction "2_2") (pintype "passive"))
      (node (ref "R7") (pin "2") (pinfunction "2_2") (pintype "passive"))
      (node (ref "R8") (pin "2") (pinfunction "2_2") (pintype "passive"))
      (node (ref "RECEIVE") (pin "A") (pinfunction "A_A") (pintype "passive"))
      (node (ref "RFID") (pin "A") (pinfunction "A_A") (pintype "passive"))
      (node (ref "SP1") (pin "P$2") (pinfunction "-_P$2") (pintype "passive"))
      (node (ref "T1") (pin "4") (pinfunction "FB_4") (pintype "bidirectional"))
      (node (ref "T2") (pin "1") (pinfunction "IN_1") (pintype "power_in"))
      (node (ref "TRANSMIT") (pin "A") (pinfunction "A_A") (pintype "passive"))
      (node (ref "U2") (pin "10") (pinfunction "VCC_10") (pintype "power_in"))
      (node (ref "U2") (pin "100") (pinfunction "AVCC_100") (pintype "power_in"))
      (node (ref "U2") (pin "31") (pinfunction "VCC1_31") (pintype "power_in"))
      (node (ref "U2") (pin "61") (pinfunction "VCC2_61") (pintype "power_in"))
      (node (ref "U2") (pin "80") (pinfunction "VCC3_80") (pintype "power_in"))
      (node (ref "X5") (pin "8") (pinfunction "8_8") (pintype "passive"))
      (node (ref "X6") (pin "5") (pinfunction "5_5") (pintype "passive"))
    )
    (net (code "3") (name "1V8A") (class "Default")
      (node (ref "C28") (pin "1") (pinfunction "1_1") (pintype "passive"))
      (node (ref "C36") (pin "+") (pinfunction "+_+") (pintype "passive"))
      (node (ref "C44") (pin "1") (pinfunction "1_1") (pintype "passive"))
      (node (ref "IC3") (pin "7") (pinfunction "1V8A_7") (pintype "power_in"))
      (node (ref "IC3") (pin "74") (pinfunction "1V8A1_74") (pintype "power_in"))
      (node (ref "L7") (pin "2") (pinfunction "2_2") (pintype "passive"))
    )
    (net (code "4") (name "1V8_OUT") (class "Default")
      (node (ref "C26") (pin "+") (pinfunction "+_+") (pintype "passive"))
      (node (ref "C29") (pin "+") (pinfunction "+_+") (pintype "passive"))
      (node (ref "C33") (pin "1") (pinfunction "1_1") (pintype "passive"))
      (node (ref "C34") (pin "1") (pinfunction "1_1") (pintype "passive"))
      (node (ref "C45") (pin "1") (pinfunction "1_1") (pintype "passive"))
      (node (ref "C46") (pin "1") (pinfunction "1_1") (pintype "passive"))
      (node (ref "IC3") (pin "11") (pinfunction "1V8-OUT_11") (pintype "power_in"))
      (node (ref "IC3") (pin "15") (pinfunction "1V8D1_15") (pintype "power_in"))
      (node (ref "IC3") (pin "16") (pinfunction "1V8D2_16") (pintype "power_in"))
      (node (ref "IC3") (pin "33") (pinfunction "1V8D3_33") (pintype "power_in"))
      (node (ref "IC3") (pin "69") (pinfunction "1V8D4_69") (pintype "power_in"))
      (node (ref "L7") (pin "1") (pinfunction "1_1") (pintype "passive"))
    )
    (net (code "5") (name "3V3A") (class "Default")
      (node (ref "C30") (pin "+") (pinfunction "+_+") (pintype "passive"))
      (node (ref "C35") (pin "1") (pinfunction "1_1") (pintype "passive"))
      (node (ref "IC3") (pin "2") (pinfunction "3V3A1_2") (pintype "power_in"))
      (node (ref "L6") (pin "2") (pinfunction "2_2") (pintype "passive"))
    )
    (net (code "6") (name "A1") (class "Default")
      (node (ref "U2") (pin "97") (pinfunction "(ADC0)PF0_97") (pintype "bidirectional"))
      (node (ref "X5") (pin "3") (pinfunction "3_3") (pintype "passive"))
      (node (ref "X6") (pin "15") (pinfunction "15_15") (pintype "passive"))
    )
    (net (code "7") (name "A2") (class "Default")
      (node (ref "U2") (pin "96") (pinfunction "(ADC1)PF1_96") (pintype "bidirectional"))
      (node (ref "X5") (pin "2") (pinfunction "2_2") (pintype "passive"))
      (node (ref "X6") (pin "16") (pinfunction "16_16") (pintype "passive"))
    )
    (net (code "8") (name "A3") (class "Default")
      (node (ref "U2") (pin "95") (pinfunction "(ADC2)PF2_95") (pintype "bidirectional"))
      (node (ref "X5") (pin "1") (pinfunction "1_1") (pintype "passive"))
      (node (ref "X6") (pin "17") (pinfunction "17_17") (pintype "passive"))
    )
    (net (code "9") (name "A4") (class "Default")
      (node (ref "U2") (pin "94") (pinfunction "(ADC3)PF3_94") (pintype "bidirectional"))
      (node (ref "X6") (pin "18") (pinfunction "18_18") (pintype "passive"))
    )
    (net (code "10") (name "A5") (class "Default")
      (node (ref "U2") (pin "93") (pinfunction "(ADC4/TCK)PF4_93") (pintype "bidirectional"))
      (node (ref "X6") (pin "19") (pinfunction "19_19") (pintype "passive"))
    )
    (net (code "11") (name "A6") (class "Default")
      (node (ref "U2") (pin "92") (pinfunction "(ADC5/TMS)PF5_92") (pintype "bidirectional"))
      (node (ref "X6") (pin "20") (pinfunction "20_20") (pintype "passive"))
    )
    (net (code "12") (name "ANT_RX") (class "Default")
      (node (ref "C14") (pin "1") (pinfunction "1_1") (pintype "passive"))
      (node (ref "IC2") (pin "29") (pinfunction "RX_29") (pintype "bidirectional"))
      (node (ref "R13") (pin "1") (pinfunction "1_1") (pintype "passive"))
      (node (ref "R9") (pin "2") (pinfunction "2_2") (pintype "passive"))
    )
    (net (code "13") (name "ANT_TX1") (class "Default")
      (node (ref "IC2") (pin "5") (pinfunction "TX1_5") (pintype "bidirectional"))
      (node (ref "L4") (pin "1") (pinfunction "1_1") (pintype "passive"))
    )
    (net (code "14") (name "ANT_TX2") (class "Default")
      (node (ref "IC2") (pin "7") (pinfunction "TX2_7") (pintype "bidirectional"))
      (node (ref "L5") (pin "1") (pinfunction "1_1") (pintype "passive"))
    )
    (net (code "15") (name "AVDD") (class "Default")
      (node (ref "C12") (pin "1") (pinfunction "1_1") (pintype "passive"))
      (node (ref "IC2") (pin "26") (pinfunction "AVDD_26") (pintype "bidirectional"))
      (node (ref "L3") (pin "1") (pinfunction "1_1") (pintype "passive"))
    )
    (net (code "16") (name "BUZZ") (class "Default")
      (node (ref "R45") (pin "1") (pinfunction "1_1") (pintype "passive"))
      (node (ref "U2") (pin "26") (pinfunction "(OC0A/OC1C/PCINT7)PB7_26") (pintype "bidirectional"))
    )
    (net (code "17") (name "COIL1") (class "Default")
      (node (ref "R14") (pin "2") (pinfunction "2_2") (pintype "passive"))
    )
    (net (code "18") (name "COIL2") (class "Default")
      (node (ref "R15") (pin "2") (pinfunction "2_2") (pintype "passive"))
    )
    (net (code "19") (name "D1") (class "Default")
      (node (ref "U2") (pin "1") (pinfunction "(OC0B)PG5_1") (pintype "bidirectional"))
      (node (ref "X6") (pin "8") (pinfunction "8_8") (pintype "passive"))
    )
    (net (code "20") (name "D2") (class "Default")
      (node (ref "U2") (pin "5") (pinfunction "(OC3A/AIN1)PE3_5") (pintype "bidirectional"))
      (node (ref "X5") (pin "6") (pinfunction "6_6") (pintype "passive"))
      (node (ref "X6") (pin "9") (pinfunction "9_9") (pintype "passive"))
    )
    (net (code "21") (name "D3") (class "Default")
      (node (ref "U2") (pin "7") (pinfunction "(OC3C/INT5)PE5_7") (pintype "bidirectional"))
      (node (ref "X6") (pin "10") (pinfunction "10_10") (pintype "passive"))
    )
    (net (code "22") (name "D4") (class "Default")
      (node (ref "U2") (pin "15") (pinfunction "PH3(OC4A)_15") (pintype "bidirectional"))
      (node (ref "X5") (pin "5") (pinfunction "5_5") (pintype "passive"))
      (node (ref "X6") (pin "11") (pinfunction "11_11") (pintype "passive"))
    )
    (net (code "23") (name "D5") (class "Default")
      (node (ref "U2") (pin "16") (pinfunction "PH4(OC4B)_16") (pintype "bidirectional"))
      (node (ref "X6") (pin "12") (pinfunction "12_12") (pintype "passive"))
    )
    (net (code "24") (name "D6") (class "Default")
      (node (ref "U2") (pin "17") (pinfunction "PH5(OC4C)_17") (pintype "bidirectional"))
      (node (ref "X5") (pin "4") (pinfunction "4_4") (pintype "passive"))
      (node (ref "X6") (pin "13") (pinfunction "13_13") (pintype "passive"))
    )
    (net (code "25") (name "D7") (class "Default")
      (node (ref "U2") (pin "18") (pinfunction "PH6(OC2B)_18") (pintype "bidirectional"))
      (node (ref "X6") (pin "14") (pinfunction "14_14") (pintype "passive"))
    )
    (net (code "26") (name "DVDD") (class "Default")
      (node (ref "C7") (pin "1") (pinfunction "1_1") (pintype "passive"))
      (node (ref "IC2") (pin "10") (pinfunction "NWR/R/NW/NWRITE_10") (pintype "bidirectional"))
      (node (ref "IC2") (pin "11") (pinfunction "NRD/NDS/NDSTRB_11") (pintype "bidirectional"))
      (node (ref "IC2") (pin "25") (pinfunction "DVDD_25") (pintype "bidirectional"))
      (node (ref "L2") (pin "1") (pinfunction "1_1") (pintype "passive"))
      (node (ref "R10") (pin "2") (pinfunction "2_2") (pintype "passive"))
      (node (ref "R12") (pin "2") (pinfunction "2_2") (pintype "passive"))
    )
    (net (code "27") (name "FDXLED") (class "Default")
      (node (ref "IC3") (pin "70") (pinfunction "FDXLED_70") (pintype "output"))
      (node (ref "R30") (pin "2") (pinfunction "2_2") (pintype "passive"))
    )
    (net (code "28") (name "GND") (class "Default")
      (node (ref "B1") (pin "-") (pinfunction "-_-") (pintype "passive"))
      (node (ref "C1") (pin "1") (pinfunction "1_1") (pintype "passive"))
      (node (ref "C10") (pin "2") (pinfunction "2_2") (pintype "passive"))
      (node (ref "C11") (pin "2") (pinfunction "2_2") (pintype "passive"))
      (node (ref "C12") (pin "2") (pinfunction "2_2") (pintype "passive"))
      (node (ref "C13") (pin "2") (pinfunction "2_2") (pintype "passive"))
      (node (ref "C14") (pin "2") (pinfunction "2_2") (pintype "passive"))
      (node (ref "C15") (pin "2") (pinfunction "2_2") (pintype "passive"))
      (node (ref "C16") (pin "1") (pinfunction "1_1") (pintype "passive"))
      (node (ref "C2") (pin "1") (pinfunction "1_1") (pintype "passive"))
      (node (ref "C22") (pin "2") (pinfunction "2_2") (pintype "passive"))
      (node (ref "C23") (pin "1") (pinfunction "1_1") (pintype "passive"))
      (node (ref "C24") (pin "2") (pinfunction "2_2") (pintype "passive"))
      (node (ref "C25") (pin "1") (pinfunction "1_1") (pintype "passive"))
      (node (ref "C26") (pin "-") (pinfunction "-_-") (pintype "passive"))
      (node (ref "C27") (pin "-") (pinfunction "-_-") (pintype "passive"))
      (node (ref "C28") (pin "2") (pinfunction "2_2") (pintype "passive"))
      (node (ref "C29") (pin "-") (pinfunction "-_-") (pintype "passive"))
      (node (ref "C3") (pin "1") (pinfunction "1_1") (pintype "passive"))
      (node (ref "C30") (pin "-") (pinfunction "-_-") (pintype "passive"))
      (node (ref "C31") (pin "2") (pinfunction "2_2") (pintype "passive"))
      (node (ref "C32") (pin "2") (pinfunction "2_2") (pintype "passive"))
      (node (ref "C33") (pin "2") (pinfunction "2_2") (pintype "passive"))
      (node (ref "C34") (pin "2") (pinfunction "2_2") (pintype "passive"))
      (node (ref "C35") (pin "2") (pinfunction "2_2") (pintype "passive"))
      (node (ref "C36") (pin "-") (pinfunction "-_-") (pintype "passive"))
      (node (ref "C37") (pin "2") (pinfunction "2_2") (pintype "passive"))
      (node (ref "C38") (pin "2") (pinfunction "2_2") (pintype "passive"))
      (node (ref "C39") (pin "2") (pinfunction "2_2") (pintype "passive"))
      (node (ref "C4") (pin "2") (pinfunction "2_2") (pintype "passive"))
      (node (ref "C40") (pin "2") (pinfunction "2_2") (pintype "passive"))
      (node (ref "C41") (pin "2") (pinfunction "2_2") (pintype "passive"))
      (node (ref "C42") (pin "2") (pinfunction "2_2") (pintype "passive"))
      (node (ref "C43") (pin "2") (pinfunction "2_2") (pintype "passive"))
      (node (ref "C44") (pin "2") (pinfunction "2_2") (pintype "passive"))
      (node (ref "C45") (pin "2") (pinfunction "2_2") (pintype "passive"))
      (node (ref "C46") (pin "2") (pinfunction "2_2") (pintype "passive"))
      (node (ref "C47") (pin "-") (pinfunction "-_-") (pintype "passive"))
      (node (ref "C48") (pin "-") (pinfunction "-_-") (pintype "passive"))
      (node (ref "C49") (pin "-") (pinfunction "-_-") (pintype "passive"))
      (node (ref "C5") (pin "2") (pinfunction "2_2") (pintype "passive"))
      (node (ref "C50") (pin "-") (pinfunction "-_-") (pintype "passive"))
      (node (ref "C51") (pin "-") (pinfunction "-_-") (pintype "passive"))
      (node (ref "C52") (pin "2") (pinfunction "2_2") (pintype "passive"))
      (node (ref "C53") (pin "2") (pinfunction "2_2") (pintype "passive"))
      (node (ref "C54") (pin "2") (pinfunction "2_2") (pintype "passive"))
      (node (ref "C55") (pin "2") (pinfunction "2_2") (pintype "passive"))
      (node (ref "C56") (pin "2") (pinfunction "2_2") (pintype "passive"))
      (node (ref "C57") (pin "2") (pinfunction "2_2") (pintype "passive"))
      (node (ref "C58") (pin "2") (pinfunction "2_2") (pintype "passive"))
      (node (ref "C59") (pin "2") (pinfunction "2_2") (pintype "passive"))
      (node (ref "C6") (pin "2") (pinfunction "2_2") (pintype "passive"))
      (node (ref "C60") (pin "2") (pinfunction "2_2") (pintype "passive"))
      (node (ref "C7") (pin "2") (pinfunction "2_2") (pintype "passive"))
      (node (ref "C8") (pin "2") (pinfunction "2_2") (pintype "passive"))
      (node (ref "C9") (pin "2") (pinfunction "2_2") (pintype "passive"))
      (node (ref "D4") (pin "A") (pinfunction "A_A") (pintype "passive"))
      (node (ref "FTDI") (pin "6") (pinfunction "6_6") (pintype "bidirectional"))
      (node (ref "IC1") (pin "6") (pinfunction "GND_6") (pintype "power_in"))
      (node (ref "IC2") (pin "12") (pinfunction "DVSS_12") (pintype "bidirectional"))
      (node (ref "IC2") (pin "23") (pinfunction "A1_23") (pintype "bidirectional"))
      (node (ref "IC2") (pin "28") (pinfunction "AVSS_28") (pintype "bidirectional"))
      (node (ref "IC2") (pin "8") (pinfunction "TVSS_8") (pintype "bidirectional"))
      (node (ref "IC2") (pin "9") (pinfunction "NCS_9") (pintype "bidirectional"))
      (node (ref "IC3") (pin "10") (pinfunction "GNDA2_10") (pintype "power_in"))
      (node (ref "IC3") (pin "13") (pinfunction "GNDD1_13") (pintype "power_in"))
      (node (ref "IC3") (pin "14") (pinfunction "GNDD2_14") (pintype "power_in"))
      (node (ref "IC3") (pin "17") (pinfunction "GNDD3_17") (pintype "power_in"))
      (node (ref "IC3") (pin "19") (pinfunction "D7_19") (pintype "input"))
      (node (ref "IC3") (pin "20") (pinfunction "D6_20") (pintype "input"))
      (node (ref "IC3") (pin "21") (pinfunction "D5_21") (pintype "input"))
      (node (ref "IC3") (pin "22") (pinfunction "D4_22") (pintype "input"))
      (node (ref "IC3") (pin "23") (pinfunction "D3_23") (pintype "input"))
      (node (ref "IC3") (pin "24") (pinfunction "D2_24") (pintype "input"))
      (node (ref "IC3") (pin "25") (pinfunction "D1_25") (pintype "input"))
      (node (ref "IC3") (pin "26") (pinfunction "D0_26") (pintype "input"))
      (node (ref "IC3") (pin "32") (pinfunction "GNDD4_32") (pintype "power_in"))
      (node (ref "IC3") (pin "34") (pinfunction "TEST3_34") (pintype "input"))
      (node (ref "IC3") (pin "35") (pinfunction "TEST2_35") (pintype "input"))
      (node (ref "IC3") (pin "36") (pinfunction "TEST1_36") (pintype "input"))
      (node (ref "IC3") (pin "37") (pinfunction "TEST0_37") (pintype "input"))
      (node (ref "IC3") (pin "38") (pinfunction "A14_38") (pintype "input"))
      (node (ref "IC3") (pin "39") (pinfunction "A13_39") (pintype "input"))
      (node (ref "IC3") (pin "4") (pinfunction "GNDA1_4") (pintype "power_in"))
      (node (ref "IC3") (pin "40") (pinfunction "A12_40") (pintype "input"))
      (node (ref "IC3") (pin "41") (pinfunction "A11_41") (pintype "input"))
      (node (ref "IC3") (pin "42") (pinfunction "A10_42") (pintype "input"))
      (node (ref "IC3") (pin "43") (pinfunction "GNDD5_43") (pintype "power_in"))
      (node (ref "IC3") (pin "45") (pinfunction "A9_45") (pintype "input"))
      (node (ref "IC3") (pin "46") (pinfunction "A8_46") (pintype "input"))
      (node (ref "IC3") (pin "47") (pinfunction "A7_47") (pintype "input"))
      (node (ref "IC3") (pin "48") (pinfunction "A6_48") (pintype "input"))
      (node (ref "IC3") (pin "49") (pinfunction "A5_49") (pintype "input"))
      (node (ref "IC3") (pin "50") (pinfunction "A4_50") (pintype "input"))
      (node (ref "IC3") (pin "51") (pinfunction "A3_51") (pintype "input"))
      (node (ref "IC3") (pin "52") (pinfunction "A2_52") (pintype "input"))
      (node (ref "IC3") (pin "53") (pinfunction "A1_53") (pintype "input"))
      (node (ref "IC3") (pin "54") (pinfunction "A0_54") (pintype "input"))
      (node (ref "IC3") (pin "63") (pinfunction "OPMODE0_63") (pintype "input"))
      (node (ref "IC3") (pin "64") (pinfunction "OPMODE1_64") (pintype "input"))
      (node (ref "IC3") (pin "65") (pinfunction "OPMODE2_65") (pintype "input"))
      (node (ref "IC3") (pin "68") (pinfunction "GNDD6_68") (pintype "power_in"))
      (node (ref "IC3") (pin "77") (pinfunction "GNDA3_77") (pintype "power_in"))
      (node (ref "IC4") (pin "1") (pinfunction "VSS_1") (pintype "bidirectional"))
      (node (ref "ISP") (pin "6") (pinfunction "6_6") (pintype "bidirectional"))
      (node (ref "P1") (pin "11") (pinfunction "VSYNC_11") (pintype "bidirectional"))
      (node (ref "P1") (pin "12") (pinfunction "HSYNC_12") (pintype "bidirectional"))
      (node (ref "P1") (pin "13") (pinfunction "DOTCLK_13") (pintype "bidirectional"))
      (node (ref "P1") (pin "14") (pinfunction "DE_14") (pintype "bidirectional"))
      (node (ref "P1") (pin "15") (pinfunction "DB17_15") (pintype "bidirectional"))
      (node (ref "P1") (pin "16") (pinfunction "DB16_16") (pintype "bidirectional"))
      (node (ref "P1") (pin "17") (pinfunction "DB15_17") (pintype "bidirectional"))
      (node (ref "P1") (pin "18") (pinfunction "DB14_18") (pintype "bidirectional"))
      (node (ref "P1") (pin "19") (pinfunction "DB13_19") (pintype "bidirectional"))
      (node (ref "P1") (pin "20") (pinfunction "DB12_20") (pintype "bidirectional"))
      (node (ref "P1") (pin "21") (pinfunction "DB11_21") (pintype "bidirectional"))
      (node (ref "P1") (pin "22") (pinfunction "DB10_22") (pintype "bidirectional"))
      (node (ref "P1") (pin "23") (pinfunction "DB9_23") (pintype "bidirectional"))
      (node (ref "P1") (pin "24") (pinfunction "DB8_24") (pintype "bidirectional"))
      (node (ref "P1") (pin "25") (pinfunction "DB7_25") (pintype "bidirectional"))
      (node (ref "P1") (pin "26") (pinfunction "DB6_26") (pintype "bidirectional"))
      (node (ref "P1") (pin "27") (pinfunction "DB5_27") (pintype "bidirectional"))
      (node (ref "P1") (pin "28") (pinfunction "DB4_28") (pintype "bidirectional"))
      (node (ref "P1") (pin "29") (pinfunction "DB3_29") (pintype "bidirectional"))
      (node (ref "P1") (pin "30") (pinfunction "DB2_30") (pintype "bidirectional"))
      (node (ref "P1") (pin "31") (pinfunction "DB1_31") (pintype "bidirectional"))
      (node (ref "P1") (pin "32") (pinfunction "DB0_32") (pintype "bidirectional"))
      (node (ref "P1") (pin "43") (pinfunction "GND_43") (pintype "bidirectional"))
      (node (ref "P1") (pin "48") (pinfunction "GND_48") (pintype "bidirectional"))
      (node (ref "P1") (pin "49") (pinfunction "GND_49") (pintype "bidirectional"))
      (node (ref "P1") (pin "50") (pinfunction "GND_50") (pintype "bidirectional"))
      (node (ref "P1") (pin "6") (pinfunction "IM0_6") (pintype "bidirectional"))
      (node (ref "Q1") (pin "2") (pinfunction "E_2") (pintype "passive"))
      (node (ref "Q3") (pin "2") (pinfunction "S_2") (pintype "bidirectional"))
      (node (ref "R11") (pin "1") (pinfunction "1_1") (pintype "passive"))
      (node (ref "R16") (pin "1") (pinfunction "1_1") (pintype "passive"))
      (node (ref "R31") (pin "2") (pinfunction "2_2") (pintype "passive"))
      (node (ref "T1") (pin "3") (pinfunction "GND_3") (pintype "bidirectional"))
      (node (ref "T1") (pin "5") (pinfunction "~{ON}/OFF_5") (pintype "bidirectional"))
      (node (ref "T1") (pin "TAB") (pinfunction "GND_TAB") (pintype "bidirectional"))
      (node (ref "T2") (pin "2") (pinfunction "GND_2") (pintype "power_in"))
      (node (ref "T2") (pin "4") (pinfunction "GND_4") (pintype "power_in"))
      (node (ref "T3") (pin "2") (pinfunction "E_2") (pintype "passive"))
      (node (ref "U1") (pin "8") (pinfunction "GND_8") (pintype "bidirectional"))
      (node (ref "U2") (pin "11") (pinfunction "GND_11") (pintype "power_in"))
      (node (ref "U2") (pin "32") (pinfunction "GND1_32") (pintype "power_in"))
      (node (ref "U2") (pin "62") (pinfunction "GND2_62") (pintype "power_in"))
      (node (ref "U2") (pin "81") (pinfunction "GND3_81") (pintype "power_in"))
      (node (ref "U2") (pin "99") (pinfunction "AGND_99") (pintype "power_in"))
      (node (ref "X1") (pin "10") (pinfunction "VC1-_10") (pintype "power_in"))
      (node (ref "X1") (pin "Z1") (pinfunction "SHIELD_Z1") (pintype "bidirectional"))
      (node (ref "X1") (pin "Z2") (pinfunction "SHIELD_Z2") (pintype "bidirectional"))
      (node (ref "X3") (pin "6") (pinfunction "VSS_6") (pintype "power_in"))
      (node (ref "X3") (pin "MT1") (pinfunction "GND_MT1") (pintype "power_in"))
      (node (ref "X3") (pin "MT2") (pinfunction "GND1_MT2") (pintype "power_in"))
      (node (ref "X5") (pin "7") (pinfunction "7_7") (pintype "passive"))
      (node (ref "X6") (pin "7") (pinfunction "7_7") (pintype "passive"))
    )
    (net (code "29") (name "LED_RFID") (class "Default")
      (node (ref "R47") (pin "1") (pinfunction "1_1") (pintype "passive"))
      (node (ref "U2") (pin "36") (pinfunction "PL1(ICP5)_36") (pintype "bidirectional"))
    )
    (net (code "30") (name "LINKLED") (class "Default")
      (node (ref "IC3") (pin "66") (pinfunction "LINKLED_66") (pintype "output"))
      (node (ref "R29") (pin "2") (pinfunction "2_2") (pintype "passive"))
    )
    (net (code "31") (name "MISO") (class "Default")
      (node (ref "IC1") (pin "12") (pinfunction "DOUT_12") (pintype "input"))
      (node (ref "IC2") (pin "13") (pinfunction "AD0/D0_13") (pintype "bidirectional"))
      (node (ref "R38") (pin "2") (pinfunction "2_2") (pintype "passive"))
      (node (ref "R39") (pin "2") (pinfunction "2_2") (pintype "passive"))
    )
    (net (code "32") (name "MISO_3V3") (class "Default")
      (node (ref "IC3") (pin "27") (pinfunction "MISO_27") (pintype "input"))
      (node (ref "P1") (pin "33") (pinfunction "SDO_33") (pintype "bidirectional"))
      (node (ref "Q6") (pin "1") (pinfunction "G_1") (pintype "passive"))
      (node (ref "R36") (pin "2") (pinfunction "2_2") (pintype "passive"))
      (node (ref "X3") (pin "3") (pinfunction "DATA_IN_3") (pintype "input"))
    )
    (net (code "33") (name "MISO_PRG") (class "Default")
      (node (ref "ISP") (pin "1") (pinfunction "1_1") (pintype "bidirectional"))
      (node (ref "R39") (pin "1") (pinfunction "1_1") (pintype "passive"))
      (node (ref "U2") (pin "22") (pinfunction "(MISO/PCINT3)PB3_22") (pintype "bidirectional"))
    )
    (net (code "34") (name "MOSI") (class "Default")
      (node (ref "IC1") (pin "14") (pinfunction "DIN_14") (pintype "input"))
      (node (ref "IC2") (pin "22") (pinfunction "A0/NWAIT/MOSI_22") (pintype "bidirectional"))
      (node (ref "R37") (pin "2") (pinfunction "2_2") (pintype "passive"))
      (node (ref "U1") (pin "3") (pinfunction "1A_3") (pintype "bidirectional"))
    )
    (net (code "35") (name "MOSI_3V3") (class "Default")
      (node (ref "IC3") (pin "28") (pinfunction "MOSI_28") (pintype "output"))
      (node (ref "P1") (pin "34") (pinfunction "SDI_34") (pintype "bidirectional"))
      (node (ref "U1") (pin "2") (pinfunction "1Y_2") (pintype "bidirectional"))
      (node (ref "X3") (pin "7") (pinfunction "DATA_OUT_7") (pintype "output"))
    )
    (net (code "36") (name "MOSI_PRG") (class "Default")
      (node (ref "ISP") (pin "4") (pinfunction "4_4") (pintype "bidirectional"))
      (node (ref "R37") (pin "1") (pinfunction "1_1") (pintype "passive"))
      (node (ref "U2") (pin "21") (pinfunction "(MOSI/PCINT2)PB2_21") (pintype "bidirectional"))
    )
    (net (code "37") (name "N$100") (class "Default")
      (node (ref "U2") (pin "13") (pinfunction "PH1(TXD2)_13") (pintype "bidirectional"))
      (node (ref "X6") (pin "2") (pinfunction "2_2") (pintype "passive"))
    )
    (net (code "38") (name "Net-(B1-PadAC1)") (class "Default")
      (node (ref "B1") (pin "AC1") (pinfunction "AC1_AC1") (pintype "passive"))
      (node (ref "X7") (pin "3") (pinfunction "3_3") (pintype "passive"))
    )
    (net (code "39") (name "Net-(B1-PadAC2)") (class "Default")
      (node (ref "B1") (pin "AC2") (pinfunction "AC2_AC2") (pintype "passive"))
      (node (ref "X7") (pin "1") (pinfunction "1_1") (pintype "passive"))
    )
    (net (code "40") (name "Net-(C15-Pad1)") (class "Default")
      (node (ref "C15") (pin "1") (pinfunction "1_1") (pintype "passive"))
      (node (ref "C18") (pin "1") (pinfunction "1_1") (pintype "passive"))
      (node (ref "C19") (pin "1") (pinfunction "1_1") (pintype "passive"))
      (node (ref "L4") (pin "2") (pinfunction "2_2") (pintype "passive"))
    )
    (net (code "41") (name "Net-(C16-Pad2)") (class "Default")
      (node (ref "C16") (pin "2") (pinfunction "2_2") (pintype "passive"))
      (node (ref "C17") (pin "1") (pinfunction "1_1") (pintype "passive"))
      (node (ref "C20") (pin "2") (pinfunction "2_2") (pintype "passive"))
      (node (ref "C21") (pin "2") (pinfunction "2_2") (pintype "passive"))
      (node (ref "L5") (pin "2") (pinfunction "2_2") (pintype "passive"))
    )
    (net (code "42") (name "Net-(C17-Pad2)") (class "Default")
      (node (ref "C17") (pin "2") (pinfunction "2_2") (pintype "passive"))
      (node (ref "R13") (pin "2") (pinfunction "2_2") (pintype "passive"))
    )
    (net (code "43") (name "Net-(C18-Pad2)") (class "Default")
      (node (ref "C18") (pin "2") (pinfunction "2_2") (pintype "passive"))
      (node (ref "C19") (pin "2") (pinfunction "2_2") (pintype "passive"))
      (node (ref "C22") (pin "1") (pinfunction "1_1") (pintype "passive"))
      (node (ref "C24") (pin "1") (pinfunction "1_1") (pintype "passive"))
      (node (ref "R14") (pin "1") (pinfunction "1_1") (pintype "passive"))
    )
    (net (code "44") (name "Net-(C20-Pad1)") (class "Default")
      (node (ref "C20") (pin "1") (pinfunction "1_1") (pintype "passive"))
      (node (ref "C21") (pin "1") (pinfunction "1_1") (pintype "passive"))
      (node (ref "C23") (pin "2") (pinfunction "2_2") (pintype "passive"))
      (node (ref "C25") (pin "2") (pinfunction "2_2") (pintype "passive"))
      (node (ref "R15") (pin "1") (pinfunction "1_1") (pintype "passive"))
    )
    (net (code "45") (name "Net-(C38-Pad1)") (class "Default")
      (node (ref "C38") (pin "1") (pinfunction "1_1") (pintype "passive"))
      (node (ref "R19") (pin "1") (pinfunction "1_1") (pintype "passive"))
      (node (ref "R20") (pin "1") (pinfunction "1_1") (pintype "passive"))
    )
    (net (code "46") (name "Net-(C39-Pad1)") (class "Default")
      (node (ref "C39") (pin "1") (pinfunction "1_1") (pintype "passive"))
      (node (ref "R21") (pin "1") (pinfunction "1_1") (pintype "passive"))
      (node (ref "R22") (pin "1") (pinfunction "1_1") (pintype "passive"))
    )
    (net (code "47") (name "Net-(COLLISION-PadC)") (class "Default")
      (node (ref "COLLISION") (pin "C") (pinfunction "C_C") (pintype "passive"))
      (node (ref "R27") (pin "2") (pinfunction "2_2") (pintype "passive"))
    )
    (net (code "48") (name "Net-(D1-A)") (class "Default")
      (node (ref "D1") (pin "1") (pinfunction "A_1") (pintype "passive"))
      (node (ref "P1") (pin "10") (pinfunction "RESET_10") (pintype "bidirectional"))
      (node (ref "R3") (pin "1") (pinfunction "1_1") (pintype "passive"))
    )
    (net (code "49") (name "Net-(D2-A)") (class "Default")
      (node (ref "D2") (pin "1") (pinfunction "A_1") (pintype "passive"))
      (node (ref "IC2") (pin "31") (pinfunction "RSTPD_31") (pintype "bidirectional"))
      (node (ref "R10") (pin "1") (pinfunction "1_1") (pintype "passive"))
      (node (ref "R11") (pin "2") (pinfunction "2_2") (pintype "passive"))
    )
    (net (code "50") (name "Net-(D3-A)") (class "Default")
      (node (ref "C41") (pin "1") (pinfunction "1_1") (pintype "passive"))
      (node (ref "D3") (pin "1") (pinfunction "A_1") (pintype "passive"))
      (node (ref "IC3") (pin "59") (pinfunction "*RESET_59") (pintype "input"))
      (node (ref "R24") (pin "1") (pinfunction "1_1") (pintype "passive"))
    )
    (net (code "51") (name "Net-(IC2-AUX)") (class "Default")
      (node (ref "IC2") (pin "27") (pinfunction "AUX_27") (pintype "bidirectional"))
      (node (ref "TP2") (pin "TP") (pinfunction "TP_TP") (pintype "input"))
    )
    (net (code "52") (name "Net-(IC2-MFOUT)") (class "Default")
      (node (ref "IC2") (pin "4") (pinfunction "MFOUT_4") (pintype "bidirectional"))
      (node (ref "TP1") (pin "TP") (pinfunction "TP_TP") (pintype "input"))
    )
    (net (code "53") (name "Net-(IC2-OSCIN)") (class "Default")
      (node (ref "C10") (pin "1") (pinfunction "1_1") (pintype "passive"))
      (node (ref "IC2") (pin "1") (pinfunction "OSCIN_1") (pintype "bidirectional"))
      (node (ref "Q2") (pin "2") (pinfunction "2_2") (pintype "passive"))
    )
    (net (code "54") (name "Net-(IC2-OSCOUT)") (class "Default")
      (node (ref "C11") (pin "1") (pinfunction "1_1") (pintype "passive"))
      (node (ref "IC2") (pin "32") (pinfunction "OSCOUT_32") (pintype "bidirectional"))
      (node (ref "Q2") (pin "1") (pinfunction "1_1") (pintype "passive"))
    )
    (net (code "55") (name "Net-(IC2-VMID)") (class "Default")
      (node (ref "IC2") (pin "30") (pinfunction "VMID_30") (pintype "bidirectional"))
      (node (ref "R9") (pin "1") (pinfunction "1_1") (pintype "passive"))
    )
    (net (code "56") (name "Net-(IC3-COLLED)") (class "Default")
      (node (ref "IC3") (pin "71") (pinfunction "COLLED_71") (pintype "output"))
      (node (ref "R27") (pin "1") (pinfunction "1_1") (pintype "passive"))
    )
    (net (code "57") (name "Net-(IC3-RSET-BG)") (class "Default")
      (node (ref "IC3") (pin "1") (pinfunction "RSET-BG_1") (pintype "input"))
      (node (ref "R18") (pin "2") (pinfunction "2_2") (pintype "passive"))
    )
    (net (code "58") (name "Net-(IC3-RXLED)") (class "Default")
      (node (ref "IC3") (pin "72") (pinfunction "RXLED_72") (pintype "output"))
      (node (ref "R26") (pin "1") (pinfunction "1_1") (pintype "passive"))
    )
    (net (code "59") (name "Net-(IC3-SEN)") (class "Default")
      (node (ref "IC3") (pin "31") (pinfunction "SEN_31") (pintype "input"))
      (node (ref "Q3") (pin "3") (pinfunction "D_3") (pintype "bidirectional"))
      (node (ref "R17") (pin "2") (pinfunction "2_2") (pintype "passive"))
    )
    (net (code "60") (name "Net-(IC3-SPDLED)") (class "Default")
      (node (ref "IC3") (pin "67") (pinfunction "SPDLED_67") (pintype "output"))
      (node (ref "R28") (pin "1") (pinfunction "1_1") (pintype "passive"))
    )
    (net (code "61") (name "Net-(IC3-TXLED)") (class "Default")
      (node (ref "IC3") (pin "73") (pinfunction "TXLED_73") (pintype "output"))
      (node (ref "R25") (pin "1") (pinfunction "1_1") (pintype "passive"))
    )
    (net (code "62") (name "Net-(IC3-XTLN)") (class "Default")
      (node (ref "C43") (pin "1") (pinfunction "1_1") (pintype "passive"))
      (node (ref "IC3") (pin "75") (pinfunction "XTLN_75") (pintype "output"))
      (node (ref "Q4") (pin "1") (pinfunction "1_1") (pintype "passive"))
      (node (ref "R23") (pin "1") (pinfunction "1_1") (pintype "passive"))
    )
    (net (code "63") (name "Net-(IC3-XTLP)") (class "Default")
      (node (ref "C42") (pin "1") (pinfunction "1_1") (pintype "passive"))
      (node (ref "IC3") (pin "76") (pinfunction "XTLP_76") (pintype "output"))
      (node (ref "Q4") (pin "2") (pinfunction "2_2") (pintype "passive"))
      (node (ref "R23") (pin "2") (pinfunction "2_2") (pintype "passive"))
    )
    (net (code "64") (name "Net-(LINK-SPEED-PadC)") (class "Default")
      (node (ref "LINK-SPEED") (pin "C") (pinfunction "C_C") (pintype "passive"))
      (node (ref "R28") (pin "2") (pinfunction "2_2") (pintype "passive"))
    )
    (net (code "65") (name "Net-(P1-LEDA-Pad2)") (class "Default")
      (node (ref "P1") (pin "2") (pinfunction "LEDA_2") (pintype "bidirectional"))
      (node (ref "R5") (pin "1") (pinfunction "1_1") (pintype "passive"))
    )
    (net (code "66") (name "Net-(P1-LEDA-Pad3)") (class "Default")
      (node (ref "P1") (pin "3") (pinfunction "LEDA_3") (pintype "bidirectional"))
      (node (ref "R6") (pin "1") (pinfunction "1_1") (pintype "passive"))
    )
    (net (code "67") (name "Net-(P1-LEDA-Pad4)") (class "Default")
      (node (ref "P1") (pin "4") (pinfunction "LEDA_4") (pintype "bidirectional"))
      (node (ref "R7") (pin "1") (pinfunction "1_1") (pintype "passive"))
    )
    (net (code "68") (name "Net-(P1-LEDA-Pad5)") (class "Default")
      (node (ref "P1") (pin "5") (pinfunction "LEDA_5") (pintype "bidirectional"))
      (node (ref "R8") (pin "1") (pinfunction "1_1") (pintype "passive"))
    )
    (net (code "69") (name "Net-(P1-LEDK)") (class "Default")
      (node (ref "P1") (pin "1") (pinfunction "LEDK_1") (pintype "bidirectional"))
      (node (ref "Q1") (pin "3") (pinfunction "C_3") (pintype "passive"))
    )
    (net (code "70") (name "Net-(PWR-PadC)") (class "Default")
      (node (ref "PWR") (pin "C") (pinfunction "C_C") (pintype "passive"))
      (node (ref "R31") (pin "1") (pinfunction "1_1") (pintype "passive"))
    )
    (net (code "71") (name "Net-(Q1-B)") (class "Default")
      (node (ref "Q1") (pin "1") (pinfunction "B_1") (pintype "passive"))
      (node (ref "R2") (pin "2") (pinfunction "2_2") (pintype "passive"))
    )
    (net (code "72") (name "Net-(Q5-D)") (class "Default")
      (node (ref "Q5") (pin "3") (pinfunction "D_3") (pintype "passive"))
      (node (ref "R34") (pin "1") (pinfunction "1_1") (pintype "passive"))
    )
    (net (code "73") (name "Net-(Q5-S)") (class "Default")
      (node (ref "Q5") (pin "2") (pinfunction "S_2") (pintype "passive"))
      (node (ref "R32") (pin "1") (pinfunction "1_1") (pintype "passive"))
    )
    (net (code "74") (name "Net-(Q6-D)") (class "Default")
      (node (ref "Q6") (pin "3") (pinfunction "D_3") (pintype "passive"))
      (node (ref "R38") (pin "1") (pinfunction "1_1") (pintype "passive"))
    )
    (net (code "75") (name "Net-(Q6-S)") (class "Default")
      (node (ref "Q6") (pin "2") (pinfunction "S_2") (pintype "passive"))
      (node (ref "R36") (pin "1") (pinfunction "1_1") (pintype "passive"))
    )
    (net (code "76") (name "Net-(R16-Pad2)") (class "Default")
      (node (ref "R16") (pin "2") (pinfunction "2_2") (pintype "passive"))
      (node (ref "R18") (pin "1") (pinfunction "1_1") (pintype "passive"))
    )
    (net (code "77") (name "Net-(R25-Pad2)") (class "Default")
      (node (ref "R25") (pin "2") (pinfunction "2_2") (pintype "passive"))
      (node (ref "TRANSMIT") (pin "C") (pinfunction "C_C") (pintype "passive"))
    )
    (net (code "78") (name "Net-(R26-Pad2)") (class "Default")
      (node (ref "R26") (pin "2") (pinfunction "2_2") (pintype "passive"))
      (node (ref "RECEIVE") (pin "C") (pinfunction "C_C") (pintype "passive"))
    )
    (net (code "79") (name "Net-(R47-Pad2)") (class "Default")
      (node (ref "R47") (pin "2") (pinfunction "2_2") (pintype "passive"))
      (node (ref "RFID") (pin "C") (pinfunction "C_C") (pintype "passive"))
    )
    (net (code "80") (name "Net-(SP1-+)") (class "Default")
      (node (ref "R44") (pin "1") (pinfunction "1_1") (pintype "passive"))
      (node (ref "SP1") (pin "P$1") (pinfunction "+_P$1") (pintype "passive"))
      (node (ref "T3") (pin "3") (pinfunction "C_3") (pintype "passive"))
    )
    (net (code "81") (name "Net-(T1-VOUT)") (class "Default")
      (node (ref "D4") (pin "C") (pinfunction "C_C") (pintype "passive"))
      (node (ref "L8") (pin "1") (pinfunction "1_1") (pintype "passive"))
      (node (ref "T1") (pin "2") (pinfunction "VOUT_2") (pintype "bidirectional"))
    )
    (net (code "82") (name "Net-(T3-B)") (class "Default")
      (node (ref "R45") (pin "2") (pinfunction "2_2") (pintype "passive"))
      (node (ref "T3") (pin "1") (pinfunction "B_1") (pintype "passive"))
    )
    (net (code "83") (name "Net-(U2-XTAL1)") (class "Default")
      (node (ref "C54") (pin "1") (pinfunction "1_1") (pintype "passive"))
      (node (ref "Q7") (pin "1") (pinfunction "1_1") (pintype "passive"))
      (node (ref "U2") (pin "34") (pinfunction "XTAL1_34") (pintype "input"))
    )
    (net (code "84") (name "Net-(U2-XTAL2)") (class "Default")
      (node (ref "C53") (pin "1") (pinfunction "1_1") (pintype "passive"))
      (node (ref "Q7") (pin "2") (pinfunction "2_2") (pintype "passive"))
      (node (ref "U2") (pin "33") (pinfunction "XTAL2_33") (pintype "output"))
    )
    (net (code "85") (name "Net-(X1A-RCT)") (class "Default")
      (node (ref "C37") (pin "1") (pinfunction "1_1") (pintype "passive"))
      (node (ref "X1") (pin "3") (pinfunction "RCT_3") (pintype "bidirectional"))
      (node (ref "X1") (pin "4") (pinfunction "TCT_4") (pintype "bidirectional"))
    )
    (net (code "86") (name "Net-(X1B-C)") (class "Default")
      (node (ref "R29") (pin "1") (pinfunction "1_1") (pintype "passive"))
      (node (ref "X1") (pin "11") (pinfunction "C_11") (pintype "passive"))
    )
    (net (code "87") (name "Net-(X1C-C)") (class "Default")
      (node (ref "R30") (pin "1") (pinfunction "1_1") (pintype "passive"))
      (node (ref "X1") (pin "13") (pinfunction "C_13") (pintype "passive"))
    )
    (net (code "88") (name "Net-(X3-DAT1)") (class "Default")
      (node (ref "R35") (pin "1") (pinfunction "1_1") (pintype "passive"))
      (node (ref "X3") (pin "8") (pinfunction "DAT1_8") (pintype "bidirectional"))
    )
    (net (code "89") (name "Net-(X3-DAT2)") (class "Default")
      (node (ref "R33") (pin "1") (pinfunction "1_1") (pintype "passive"))
      (node (ref "X3") (pin "1") (pinfunction "DAT2_1") (pintype "bidirectional"))
    )
    (net (code "90") (name "RX2") (class "Default")
      (node (ref "U2") (pin "12") (pinfunction "PH0(RXD2)_12") (pintype "bidirectional"))
      (node (ref "X6") (pin "1") (pinfunction "1_1") (pintype "passive"))
    )
    (net (code "91") (name "RXD") (class "Default")
      (node (ref "FTDI") (pin "2") (pinfunction "2_2") (pintype "bidirectional"))
      (node (ref "U2") (pin "2") (pinfunction "(RXD0/PCIN8)PE0_2") (pintype "bidirectional"))
    )
    (net (code "92") (name "RXI_N") (class "Default")
      (node (ref "IC3") (pin "6") (pinfunction "RXIN_6") (pintype "input"))
      (node (ref "R22") (pin "2") (pinfunction "2_2") (pintype "passive"))
      (node (ref "X1") (pin "2") (pinfunction "RD-_2") (pintype "bidirectional"))
    )
    (net (code "93") (name "RXI_P") (class "Default")
      (node (ref "IC3") (pin "5") (pinfunction "RXIP_5") (pintype "input"))
      (node (ref "R21") (pin "2") (pinfunction "2_2") (pintype "passive"))
      (node (ref "X1") (pin "1") (pinfunction "RD+_1") (pintype "bidirectional"))
    )
    (net (code "94") (name "SCK") (class "Default")
      (node (ref "IC1") (pin "16") (pinfunction "DCLK_16") (pintype "output"))
      (node (ref "IC2") (pin "24") (pinfunction "A2/SCK_24") (pintype "bidirectional"))
      (node (ref "R40") (pin "2") (pinfunction "2_2") (pintype "passive"))
      (node (ref "U1") (pin "5") (pinfunction "2A_5") (pintype "bidirectional"))
    )
    (net (code "95") (name "SCK_3V3") (class "Default")
      (node (ref "IC3") (pin "30") (pinfunction "SCLK_30") (pintype "input"))
      (node (ref "P1") (pin "37") (pinfunction "D/CX_37") (pintype "bidirectional"))
      (node (ref "U1") (pin "4") (pinfunction "2Y_4") (pintype "bidirectional"))
      (node (ref "X3") (pin "5") (pinfunction "SCLK_5") (pintype "input"))
    )
    (net (code "96") (name "SCK_PRG") (class "Default")
      (node (ref "ISP") (pin "3") (pinfunction "3_3") (pintype "bidirectional"))
      (node (ref "R40") (pin "1") (pinfunction "1_1") (pintype "passive"))
      (node (ref "U2") (pin "20") (pinfunction "(SCK/PCINT1)PB1_20") (pintype "bidirectional"))
    )
    (net (code "97") (name "SCL") (class "Default")
      (node (ref "R48") (pin "1") (pinfunction "1_1") (pintype "passive"))
      (node (ref "U2") (pin "43") (pinfunction "(SCL/INT0)PD0_43") (pintype "bidirectional"))
      (node (ref "X5") (pin "10") (pinfunction "10_10") (pintype "passive"))
      (node (ref "X6") (pin "4") (pinfunction "4_4") (pintype "passive"))
    )
    (net (code "98") (name "SDA") (class "Default")
      (node (ref "R46") (pin "1") (pinfunction "1_1") (pintype "passive"))
      (node (ref "U2") (pin "44") (pinfunction "(SDA/INT1)PD1_44") (pintype "bidirectional"))
      (node (ref "X5") (pin "9") (pinfunction "9_9") (pintype "passive"))
      (node (ref "X6") (pin "3") (pinfunction "3_3") (pintype "passive"))
    )
    (net (code "99") (name "TFT_BL") (class "Default")
      (node (ref "R1") (pin "2") (pinfunction "2_2") (pintype "passive"))
      (node (ref "R2") (pin "1") (pinfunction "1_1") (pintype "passive"))
      (node (ref "U2") (pin "40") (pinfunction "PL5(OC5C)_40") (pintype "bidirectional"))
    )
    (net (code "100") (name "TVDD") (class "Default")
      (node (ref "C6") (pin "1") (pinfunction "1_1") (pintype "passive"))
      (node (ref "IC2") (pin "6") (pinfunction "TVDD_6") (pintype "bidirectional"))
      (node (ref "L1") (pin "1") (pinfunction "1_1") (pintype "passive"))
    )
    (net (code "101") (name "TXD") (class "Default")
      (node (ref "FTDI") (pin "3") (pinfunction "3_3") (pintype "bidirectional"))
      (node (ref "U2") (pin "3") (pinfunction "(TXD0)PE1_3") (pintype "bidirectional"))
    )
    (net (code "102") (name "TXO_N") (class "Default")
      (node (ref "IC3") (pin "9") (pinfunction "TXON_9") (pintype "output"))
      (node (ref "R20") (pin "2") (pinfunction "2_2") (pintype "passive"))
      (node (ref "X1") (pin "6") (pinfunction "TD-_6") (pintype "bidirectional"))
    )
    (net (code "103") (name "TXO_P") (class "Default")
      (node (ref "IC3") (pin "8") (pinfunction "TXOP_8") (pintype "output"))
      (node (ref "R19") (pin "2") (pinfunction "2_2") (pintype "passive"))
      (node (ref "X1") (pin "5") (pinfunction "TD+_5") (pintype "bidirectional"))
    )
    (net (code "104") (name "VCC") (class "Default")
      (node (ref "B1") (pin "+") (pinfunction "+_+") (pintype "passive"))
      (node (ref "C47") (pin "+") (pinfunction "+_+") (pintype "passive"))
      (node (ref "T1") (pin "1") (pinfunction "VIN_1") (pintype "bidirectional"))
    )
    (net (code "105") (name "VCC_NET") (class "Default")
      (node (ref "X1") (pin "9") (pinfunction "VC1+_9") (pintype "power_in"))
      (node (ref "X7") (pin "2") (pinfunction "2_2") (pintype "passive"))
    )
    (net (code "106") (name "X+") (class "Default")
      (node (ref "IC1") (pin "2") (pinfunction "X+_2") (pintype "input"))
      (node (ref "P1") (pin "44") (pinfunction "XR_44") (pintype "bidirectional"))
    )
    (net (code "107") (name "X-") (class "Default")
      (node (ref "IC1") (pin "4") (pinfunction "X-_4") (pintype "input"))
      (node (ref "P1") (pin "46") (pinfunction "XL_46") (pintype "bidirectional"))
    )
    (net (code "108") (name "Y+") (class "Default")
      (node (ref "IC1") (pin "3") (pinfunction "Y+_3") (pintype "input"))
      (node (ref "P1") (pin "45") (pinfunction "YD_45") (pintype "bidirectional"))
    )
    (net (code "109") (name "Y-") (class "Default")
      (node (ref "IC1") (pin "5") (pinfunction "Y-_5") (pintype "input"))
      (node (ref "P1") (pin "47") (pinfunction "YU_47") (pintype "bidirectional"))
    )
    (net (code "110") (name "unconnected-(FTDI-Pad1)") (class "Default")
      (node (ref "FTDI") (pin "1") (pinfunction "1_1") (pintype "bidirectional"))
    )
    (net (code "111") (name "unconnected-(FTDI-Pad5)") (class "Default")
      (node (ref "FTDI") (pin "5") (pinfunction "5_5") (pintype "bidirectional"))
    )
    (net (code "112") (name "unconnected-(IC1-AUX-Pad8)") (class "Default")
      (node (ref "IC1") (pin "8") (pinfunction "AUX_8") (pintype "input"))
    )
    (net (code "113") (name "unconnected-(IC1-BUSY-Pad13)") (class "Default")
      (node (ref "IC1") (pin "13") (pinfunction "BUSY_13") (pintype "output"))
    )
    (net (code "114") (name "unconnected-(IC1-VBAT-Pad7)") (class "Default")
      (node (ref "IC1") (pin "7") (pinfunction "VBAT_7") (pintype "input"))
    )
    (net (code "115") (name "unconnected-(IC1-VREF-Pad9)") (class "Default")
      (node (ref "IC1") (pin "9") (pinfunction "VREF_9") (pintype "bidirectional"))
    )
    (net (code "116") (name "unconnected-(IC2-AD1{slash}D1-Pad14)") (class "Default")
      (node (ref "IC2") (pin "14") (pinfunction "AD1/D1_14") (pintype "bidirectional"))
    )
    (net (code "117") (name "unconnected-(IC2-AD2{slash}D2-Pad15)") (class "Default")
      (node (ref "IC2") (pin "15") (pinfunction "AD2/D2_15") (pintype "bidirectional"))
    )
    (net (code "118") (name "unconnected-(IC2-AD3{slash}D3-Pad16)") (class "Default")
      (node (ref "IC2") (pin "16") (pinfunction "AD3/D3_16") (pintype "bidirectional"))
    )
    (net (code "119") (name "unconnected-(IC2-D4{slash}AD4-Pad17)") (class "Default")
      (node (ref "IC2") (pin "17") (pinfunction "D4/AD4_17") (pintype "bidirectional"))
    )
    (net (code "120") (name "unconnected-(IC2-D5{slash}AD5-Pad18)") (class "Default")
      (node (ref "IC2") (pin "18") (pinfunction "D5/AD5_18") (pintype "bidirectional"))
    )
    (net (code "121") (name "unconnected-(IC2-D6{slash}AD6-Pad19)") (class "Default")
      (node (ref "IC2") (pin "19") (pinfunction "D6/AD6_19") (pintype "bidirectional"))
    )
    (net (code "122") (name "unconnected-(IC2-D7{slash}AD7-Pad20)") (class "Default")
      (node (ref "IC2") (pin "20") (pinfunction "D7/AD7_20") (pintype "bidirectional"))
    )
    (net (code "123") (name "unconnected-(IC2-MFIN-Pad3)") (class "Default")
      (node (ref "IC2") (pin "3") (pinfunction "MFIN_3") (pintype "bidirectional"))
    )
    (net (code "124") (name "unconnected-(IC3-*CS-Pad55)") (class "Default")
      (node (ref "IC3") (pin "55") (pinfunction "*CS_55") (pintype "input"))
    )
    (net (code "125") (name "unconnected-(IC3-*RD-Pad58)") (class "Default")
      (node (ref "IC3") (pin "58") (pinfunction "*RD_58") (pintype "input"))
    )
    (net (code "126") (name "unconnected-(IC3-*WR-Pad57)") (class "Default")
      (node (ref "IC3") (pin "57") (pinfunction "*WR_57") (pintype "input"))
    )
    (net (code "127") (name "unconnected-(IC3-NC-Pad3)") (class "Default")
      (node (ref "IC3") (pin "3") (pinfunction "NC_3") (pintype "no_connect"))
    )
    (net (code "128") (name "unconnected-(IC3-NC1-Pad60)") (class "Default")
      (node (ref "IC3") (pin "60") (pinfunction "NC1_60") (pintype "no_connect"))
    )
    (net (code "129") (name "unconnected-(IC3-NC2-Pad61)") (class "Default")
      (node (ref "IC3") (pin "61") (pinfunction "NC2_61") (pintype "no_connect"))
    )
    (net (code "130") (name "unconnected-(IC3-NC3-Pad62)") (class "Default")
      (node (ref "IC3") (pin "62") (pinfunction "NC3_62") (pintype "no_connect"))
    )
    (net (code "131") (name "unconnected-(IC3-NC4-Pad78)") (class "Default")
      (node (ref "IC3") (pin "78") (pinfunction "NC4_78") (pintype "no_connect"))
    )
    (net (code "132") (name "unconnected-(IC3-NC5-Pad79)") (class "Default")
      (node (ref "IC3") (pin "79") (pinfunction "NC5_79") (pintype "no_connect"))
    )
    (net (code "133") (name "unconnected-(IC3-NC6-Pad80)") (class "Default")
      (node (ref "IC3") (pin "80") (pinfunction "NC6_80") (pintype "no_connect"))
    )
    (net (code "134") (name "unconnected-(P1-TE-Pad39)") (class "Default")
      (node (ref "P1") (pin "39") (pinfunction "TE_39") (pintype "bidirectional"))
    )
    (net (code "135") (name "unconnected-(U2-(A8)PC0-Pad53)") (class "Default")
      (node (ref "U2") (pin "53") (pinfunction "(A8)PC0_53") (pintype "bidirectional"))
    )
    (net (code "136") (name "unconnected-(U2-(A9)PC1-Pad54)") (class "Default")
      (node (ref "U2") (pin "54") (pinfunction "(A9)PC1_54") (pintype "bidirectional"))
    )
    (net (code "137") (name "unconnected-(U2-(A10)PC2-Pad55)") (class "Default")
      (node (ref "U2") (pin "55") (pinfunction "(A10)PC2_55") (pintype "bidirectional"))
    )
    (net (code "138") (name "unconnected-(U2-(A11)PC3-Pad56)") (class "Default")
      (node (ref "U2") (pin "56") (pinfunction "(A11)PC3_56") (pintype "bidirectional"))
    )
    (net (code "139") (name "unconnected-(U2-(A12)PC4-Pad57)") (class "Default")
      (node (ref "U2") (pin "57") (pinfunction "(A12)PC4_57") (pintype "bidirectional"))
    )
    (net (code "140") (name "unconnected-(U2-(A13)PC5-Pad58)") (class "Default")
      (node (ref "U2") (pin "58") (pinfunction "(A13)PC5_58") (pintype "bidirectional"))
    )
    (net (code "141") (name "unconnected-(U2-(A14)PC6-Pad59)") (class "Default")
      (node (ref "U2") (pin "59") (pinfunction "(A14)PC6_59") (pintype "bidirectional"))
    )
    (net (code "142") (name "unconnected-(U2-(A15)PC7-Pad60)") (class "Default")
      (node (ref "U2") (pin "60") (pinfunction "(A15)PC7_60") (pintype "bidirectional"))
    )
    (net (code "143") (name "unconnected-(U2-(AD0)PA0-Pad78)") (class "Default")
      (node (ref "U2") (pin "78") (pinfunction "(AD0)PA0_78") (pintype "bidirectional"))
    )
    (net (code "144") (name "unconnected-(U2-(AD1)PA1-Pad77)") (class "Default")
      (node (ref "U2") (pin "77") (pinfunction "(AD1)PA1_77") (pintype "bidirectional"))
    )
    (net (code "145") (name "unconnected-(U2-(AD2)PA2-Pad76)") (class "Default")
      (node (ref "U2") (pin "76") (pinfunction "(AD2)PA2_76") (pintype "bidirectional"))
    )
    (net (code "146") (name "unconnected-(U2-(AD3)PA3-Pad75)") (class "Default")
      (node (ref "U2") (pin "75") (pinfunction "(AD3)PA3_75") (pintype "bidirectional"))
    )
    (net (code "147") (name "unconnected-(U2-(AD4)PA4-Pad74)") (class "Default")
      (node (ref "U2") (pin "74") (pinfunction "(AD4)PA4_74") (pintype "bidirectional"))
    )
    (net (code "148") (name "unconnected-(U2-(AD5)PA5-Pad73)") (class "Default")
      (node (ref "U2") (pin "73") (pinfunction "(AD5)PA5_73") (pintype "bidirectional"))
    )
    (net (code "149") (name "unconnected-(U2-(AD6)PA6-Pad72)") (class "Default")
      (node (ref "U2") (pin "72") (pinfunction "(AD6)PA6_72") (pintype "bidirectional"))
    )
    (net (code "150") (name "unconnected-(U2-(AD7)PA7-Pad71)") (class "Default")
      (node (ref "U2") (pin "71") (pinfunction "(AD7)PA7_71") (pintype "bidirectional"))
    )
    (net (code "151") (name "unconnected-(U2-(ADC6{slash}TDO)PF6-Pad91)") (class "Default")
      (node (ref "U2") (pin "91") (pinfunction "(ADC6/TDO)PF6_91") (pintype "bidirectional"))
    )
    (net (code "152") (name "unconnected-(U2-(ADC7{slash}TDI)PF7-Pad90)") (class "Default")
      (node (ref "U2") (pin "90") (pinfunction "(ADC7/TDI)PF7_90") (pintype "bidirectional"))
    )
    (net (code "153") (name "unconnected-(U2-(ALE)PG2-Pad70)") (class "Default")
      (node (ref "U2") (pin "70") (pinfunction "(ALE)PG2_70") (pintype "bidirectional"))
    )
    (net (code "154") (name "unconnected-(U2-(CLKO{slash}ICP3{slash}INT7)PE7-Pad9)") (class "Default")
      (node (ref "U2") (pin "9") (pinfunction "(CLKO/ICP3/INT7)PE7_9") (pintype "bidirectional"))
    )
    (net (code "155") (name "unconnected-(U2-(ICP1)PD4-Pad47)") (class "Default")
      (node (ref "U2") (pin "47") (pinfunction "(ICP1)PD4_47") (pintype "bidirectional"))
    )
    (net (code "156") (name "unconnected-(U2-(OC1A{slash}PCINT5)PB5-Pad24)") (class "Default")
      (node (ref "U2") (pin "24") (pinfunction "(OC1A/PCINT5)PB5_24") (pintype "bidirectional"))
    )
    (net (code "157") (name "unconnected-(U2-(OC1B{slash}PCINT6)PB6-Pad25)") (class "Default")
      (node (ref "U2") (pin "25") (pinfunction "(OC1B/PCINT6)PB6_25") (pintype "bidirectional"))
    )
    (net (code "158") (name "unconnected-(U2-(OC2A{slash}PCINT4)PB4-Pad23)") (class "Default")
      (node (ref "U2") (pin "23") (pinfunction "(OC2A/PCINT4)PB4_23") (pintype "bidirectional"))
    )
    (net (code "159") (name "unconnected-(U2-(RD)PG1-Pad52)") (class "Default")
      (node (ref "U2") (pin "52") (pinfunction "(RD)PG1_52") (pintype "bidirectional"))
    )
    (net (code "160") (name "unconnected-(U2-(SS{slash}PCINT0)PB0-Pad19)") (class "Default")
      (node (ref "U2") (pin "19") (pinfunction "(SS/PCINT0)PB0_19") (pintype "bidirectional"))
    )
    (net (code "161") (name "unconnected-(U2-(T0)PD7-Pad50)") (class "Default")
      (node (ref "U2") (pin "50") (pinfunction "(T0)PD7_50") (pintype "bidirectional"))
    )
    (net (code "162") (name "unconnected-(U2-(T1)PD6-Pad49)") (class "Default")
      (node (ref "U2") (pin "49") (pinfunction "(T1)PD6_49") (pintype "bidirectional"))
    )
    (net (code "163") (name "unconnected-(U2-(T3{slash}INT6)PE6-Pad8)") (class "Default")
      (node (ref "U2") (pin "8") (pinfunction "(T3/INT6)PE6_8") (pintype "bidirectional"))
    )
    (net (code "164") (name "unconnected-(U2-(TOSC1)PG4-Pad29)") (class "Default")
      (node (ref "U2") (pin "29") (pinfunction "(TOSC1)PG4_29") (pintype "bidirectional"))
    )
    (net (code "165") (name "unconnected-(U2-(TOSC2)PG3-Pad28)") (class "Default")
      (node (ref "U2") (pin "28") (pinfunction "(TOSC2)PG3_28") (pintype "bidirectional"))
    )
    (net (code "166") (name "unconnected-(U2-(WR)PG0-Pad51)") (class "Default")
      (node (ref "U2") (pin "51") (pinfunction "(WR)PG0_51") (pintype "bidirectional"))
    )
    (net (code "167") (name "unconnected-(U2-(XCK0{slash}AIN0)PE2-Pad4)") (class "Default")
      (node (ref "U2") (pin "4") (pinfunction "(XCK0/AIN0)PE2_4") (pintype "bidirectional"))
    )
    (net (code "168") (name "unconnected-(U2-(XCK1)PD5-Pad48)") (class "Default")
      (node (ref "U2") (pin "48") (pinfunction "(XCK1)PD5_48") (pintype "bidirectional"))
    )
    (net (code "169") (name "unconnected-(U2-AREF-Pad98)") (class "Default")
      (node (ref "U2") (pin "98") (pinfunction "AREF_98") (pintype "bidirectional"))
    )
    (net (code "170") (name "unconnected-(U2-PH2(XCK2)-Pad14)") (class "Default")
      (node (ref "U2") (pin "14") (pinfunction "PH2(XCK2)_14") (pintype "bidirectional"))
    )
    (net (code "171") (name "unconnected-(U2-PH7(T4)-Pad27)") (class "Default")
      (node (ref "U2") (pin "27") (pinfunction "PH7(T4)_27") (pintype "bidirectional"))
    )
    (net (code "172") (name "unconnected-(U2-PJ0(RXD3{slash}PCINT9)-Pad63)") (class "Default")
      (node (ref "U2") (pin "63") (pinfunction "PJ0(RXD3/PCINT9)_63") (pintype "bidirectional"))
    )
    (net (code "173") (name "unconnected-(U2-PJ1(TXD3{slash}PCINT10)-Pad64)") (class "Default")
      (node (ref "U2") (pin "64") (pinfunction "PJ1(TXD3/PCINT10)_64") (pintype "bidirectional"))
    )
    (net (code "174") (name "unconnected-(U2-PJ2(XCK3{slash}PCINT11)-Pad65)") (class "Default")
      (node (ref "U2") (pin "65") (pinfunction "PJ2(XCK3/PCINT11)_65") (pintype "bidirectional"))
    )
    (net (code "175") (name "unconnected-(U2-PJ3(PCINT12)-Pad66)") (class "Default")
      (node (ref "U2") (pin "66") (pinfunction "PJ3(PCINT12)_66") (pintype "bidirectional"))
    )
    (net (code "176") (name "unconnected-(U2-PJ4(PCINT13)-Pad67)") (class "Default")
      (node (ref "U2") (pin "67") (pinfunction "PJ4(PCINT13)_67") (pintype "bidirectional"))
    )
    (net (code "177") (name "unconnected-(U2-PJ5(PCINT14)-Pad68)") (class "Default")
      (node (ref "U2") (pin "68") (pinfunction "PJ5(PCINT14)_68") (pintype "bidirectional"))
    )
    (net (code "178") (name "unconnected-(U2-PJ6(PCINT15)-Pad69)") (class "Default")
      (node (ref "U2") (pin "69") (pinfunction "PJ6(PCINT15)_69") (pintype "bidirectional"))
    )
    (net (code "179") (name "unconnected-(U2-PJ7-Pad79)") (class "Default")
      (node (ref "U2") (pin "79") (pinfunction "PJ7_79") (pintype "bidirectional"))
    )
    (net (code "180") (name "unconnected-(U2-PK0(ADC8{slash}PCINT16)-Pad89)") (class "Default")
      (node (ref "U2") (pin "89") (pinfunction "PK0(ADC8/PCINT16)_89") (pintype "bidirectional"))
    )
    (net (code "181") (name "unconnected-(U2-PK1(ADC9{slash}PCINT17)-Pad88)") (class "Default")
      (node (ref "U2") (pin "88") (pinfunction "PK1(ADC9/PCINT17)_88") (pintype "bidirectional"))
    )
    (net (code "182") (name "unconnected-(U2-PK2(ADC10{slash}PCINT18)-Pad87)") (class "Default")
      (node (ref "U2") (pin "87") (pinfunction "PK2(ADC10/PCINT18)_87") (pintype "bidirectional"))
    )
    (net (code "183") (name "unconnected-(U2-PK3(ADC11{slash}PCINT19)-Pad86)") (class "Default")
      (node (ref "U2") (pin "86") (pinfunction "PK3(ADC11/PCINT19)_86") (pintype "bidirectional"))
    )
    (net (code "184") (name "unconnected-(U2-PK4(ADC12{slash}PCINT20)-Pad85)") (class "Default")
      (node (ref "U2") (pin "85") (pinfunction "PK4(ADC12/PCINT20)_85") (pintype "bidirectional"))
    )
    (net (code "185") (name "unconnected-(U2-PK5(ADC13{slash}PCINT21)-Pad84)") (class "Default")
      (node (ref "U2") (pin "84") (pinfunction "PK5(ADC13/PCINT21)_84") (pintype "bidirectional"))
    )
    (net (code "186") (name "unconnected-(U2-PK6(ADC14{slash}PCINT22)-Pad83)") (class "Default")
      (node (ref "U2") (pin "83") (pinfunction "PK6(ADC14/PCINT22)_83") (pintype "bidirectional"))
    )
    (net (code "187") (name "unconnected-(U2-PK7(ADC15{slash}PCINT23)-Pad82)") (class "Default")
      (node (ref "U2") (pin "82") (pinfunction "PK7(ADC15/PCINT23)_82") (pintype "bidirectional"))
    )
    (net (code "188") (name "unconnected-(U2-PL0(ICP4)-Pad35)") (class "Default")
      (node (ref "U2") (pin "35") (pinfunction "PL0(ICP4)_35") (pintype "bidirectional"))
    )
    (net (code "189") (name "unconnected-(X3-CARD_DETECT-PadCD1)") (class "Default")
      (node (ref "X3") (pin "CD1") (pinfunction "CARD_DETECT_CD1") (pintype "passive"))
    )
    (net (code "190") (name "unconnected-(X3-CARD_DETECT1-PadCD2)") (class "Default")
      (node (ref "X3") (pin "CD2") (pinfunction "CARD_DETECT1_CD2") (pintype "passive"))
    )
    (net (code "191") (name "~{PENIRQ}") (class "Default")
      (node (ref "IC1") (pin "11") (pinfunction "~{PENIRQ}_11") (pintype "output"))
      (node (ref "U2") (pin "45") (pinfunction "(RXD1/INT2)PD2_45") (pintype "bidirectional"))
    )
    (net (code "192") (name "~{RESET_3V3}") (class "Default")
      (node (ref "D1") (pin "3") (pinfunction "C_3") (pintype "passive"))
      (node (ref "D3") (pin "3") (pinfunction "C_3") (pintype "passive"))
      (node (ref "U1") (pin "10") (pinfunction "4Y_10") (pintype "bidirectional"))
    )
    (net (code "193") (name "~{RESET_PRG}") (class "Default")
      (node (ref "C60") (pin "1") (pinfunction "1_1") (pintype "passive"))
      (node (ref "D5") (pin "1") (pinfunction "A_1") (pintype "passive"))
      (node (ref "ISP") (pin "5") (pinfunction "5_5") (pintype "bidirectional"))
      (node (ref "R49") (pin "2") (pinfunction "2_2") (pintype "passive"))
      (node (ref "U2") (pin "30") (pinfunction "RESET_30") (pintype "input"))
    )
    (net (code "194") (name "~{RESET}") (class "Default")
      (node (ref "D2") (pin "3") (pinfunction "C_3") (pintype "passive"))
      (node (ref "D5") (pin "3") (pinfunction "C_3") (pintype "passive"))
      (node (ref "IC4") (pin "2") (pinfunction "~{RST}_2") (pintype "bidirectional"))
      (node (ref "U1") (pin "9") (pinfunction "4A_9") (pintype "bidirectional"))
    )
    (net (code "195") (name "~{RFID_IRQ}") (class "Default")
      (node (ref "IC2") (pin "2") (pinfunction "~{IRQ}_2") (pintype "bidirectional"))
      (node (ref "U2") (pin "6") (pinfunction "(OC3B/INT4)PE4_6") (pintype "bidirectional"))
    )
    (net (code "196") (name "~{RFID_SS}") (class "Default")
      (node (ref "IC2") (pin "21") (pinfunction "ALE/AS/NASTREB/NSS_21") (pintype "bidirectional"))
      (node (ref "R12") (pin "1") (pinfunction "1_1") (pintype "passive"))
      (node (ref "U2") (pin "39") (pinfunction "PL4(OC5B)_39") (pintype "bidirectional"))
    )
    (net (code "197") (name "~{SD_SS_3V3}") (class "Default")
      (node (ref "U1") (pin "12") (pinfunction "5Y_12") (pintype "bidirectional"))
      (node (ref "X3") (pin "2") (pinfunction "CS_2") (pintype "input"))
    )
    (net (code "198") (name "~{SD_SS}") (class "Default")
      (node (ref "R42") (pin "1") (pinfunction "1_1") (pintype "passive"))
      (node (ref "U1") (pin "11") (pinfunction "5A_11") (pintype "bidirectional"))
      (node (ref "U2") (pin "37") (pinfunction "PL2(T5)_37") (pintype "bidirectional"))
    )
    (net (code "199") (name "~{TFT_SS_3V3}") (class "Default")
      (node (ref "P1") (pin "38") (pinfunction "CSX_38") (pintype "bidirectional"))
      (node (ref "U1") (pin "6") (pinfunction "3Y_6") (pintype "bidirectional"))
    )
    (net (code "200") (name "~{TFT_SS}") (class "Default")
      (node (ref "R41") (pin "1") (pinfunction "1_1") (pintype "passive"))
      (node (ref "U1") (pin "7") (pinfunction "3A_7") (pintype "bidirectional"))
      (node (ref "U2") (pin "41") (pinfunction "PL6_41") (pintype "bidirectional"))
    )
    (net (code "201") (name "~{TOUCH_SS}") (class "Default")
      (node (ref "IC1") (pin "15") (pinfunction "~{CS}_15") (pintype "input"))
      (node (ref "R4") (pin "1") (pinfunction "1_1") (pintype "passive"))
      (node (ref "U2") (pin "42") (pinfunction "PL7_42") (pintype "bidirectional"))
    )
    (net (code "202") (name "~{WIZ_IRQ_3V3}") (class "Default")
      (node (ref "IC3") (pin "56") (pinfunction "*INT_56") (pintype "input"))
      (node (ref "Q5") (pin "1") (pinfunction "G_1") (pintype "passive"))
      (node (ref "R32") (pin "2") (pinfunction "2_2") (pintype "passive"))
    )
    (net (code "203") (name "~{WIZ_IRQ}") (class "Default")
      (node (ref "R34") (pin "2") (pinfunction "2_2") (pintype "passive"))
      (node (ref "U2") (pin "46") (pinfunction "(TXD1/INT3)PD3_46") (pintype "bidirectional"))
    )
    (net (code "204") (name "~{WIZ_SS_3V3}") (class "Default")
      (node (ref "IC3") (pin "29") (pinfunction "*SCS_29") (pintype "input"))
      (node (ref "Q3") (pin "1") (pinfunction "G_1") (pintype "bidirectional"))
      (node (ref "U1") (pin "15") (pinfunction "6Y_15") (pintype "bidirectional"))
    )
    (net (code "205") (name "~{WIZ_SS}") (class "Default")
      (node (ref "R43") (pin "1") (pinfunction "1_1") (pintype "passive"))
      (node (ref "U1") (pin "14") (pinfunction "6A_14") (pintype "bidirectional"))
      (node (ref "U2") (pin "38") (pinfunction "PL3(OC5A)_38") (pintype "bidirectional"))
    )
  )
)
